# 612_jetracer_esp32s3_030005.net
KiCad netlist of a schematic drawn in EAGLE
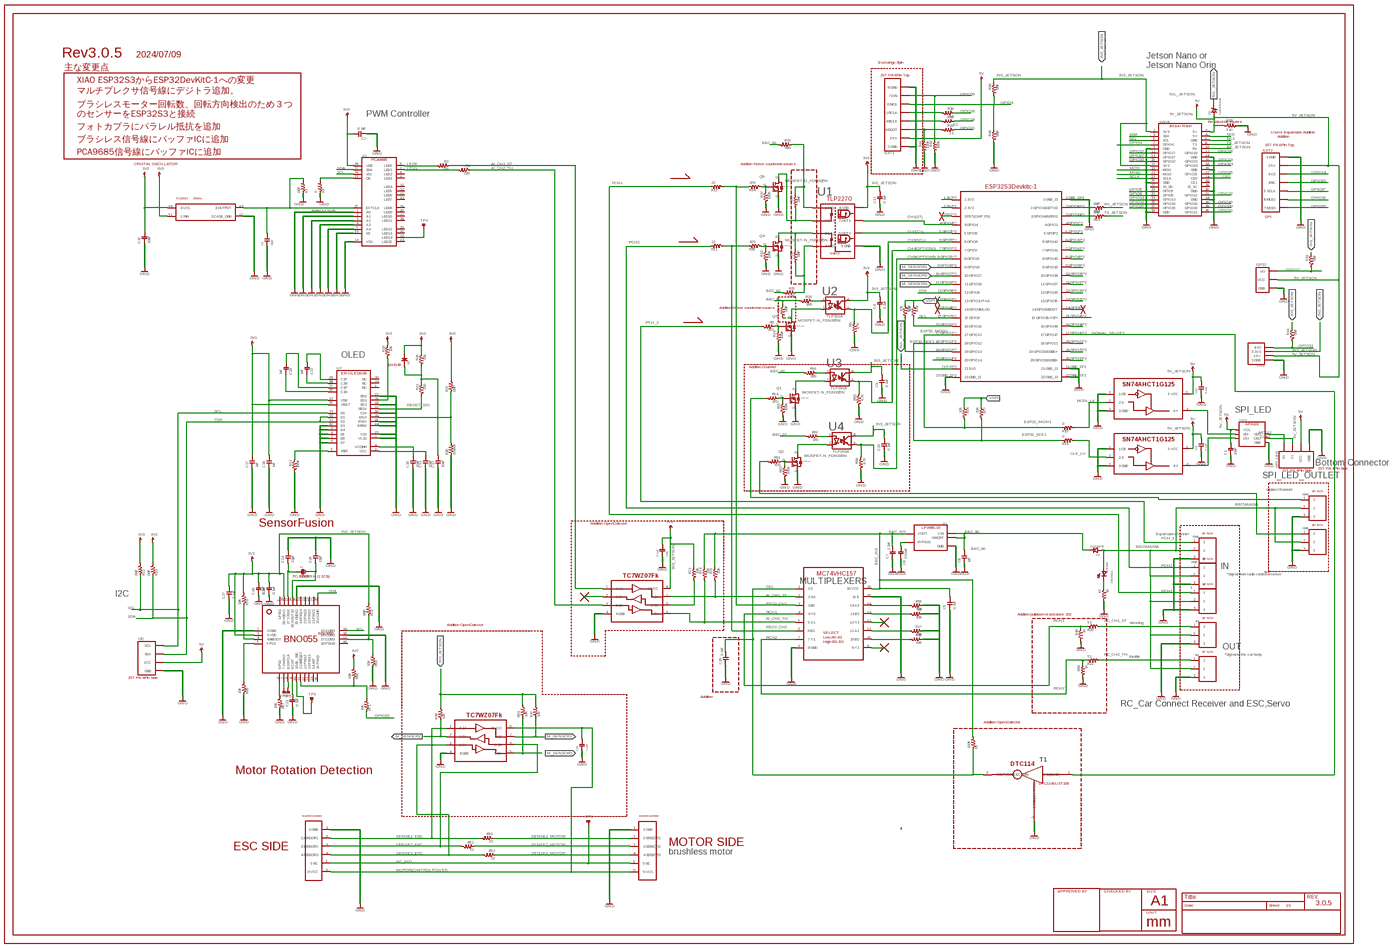
[diagram p0: schematic, sheet 1, overview]
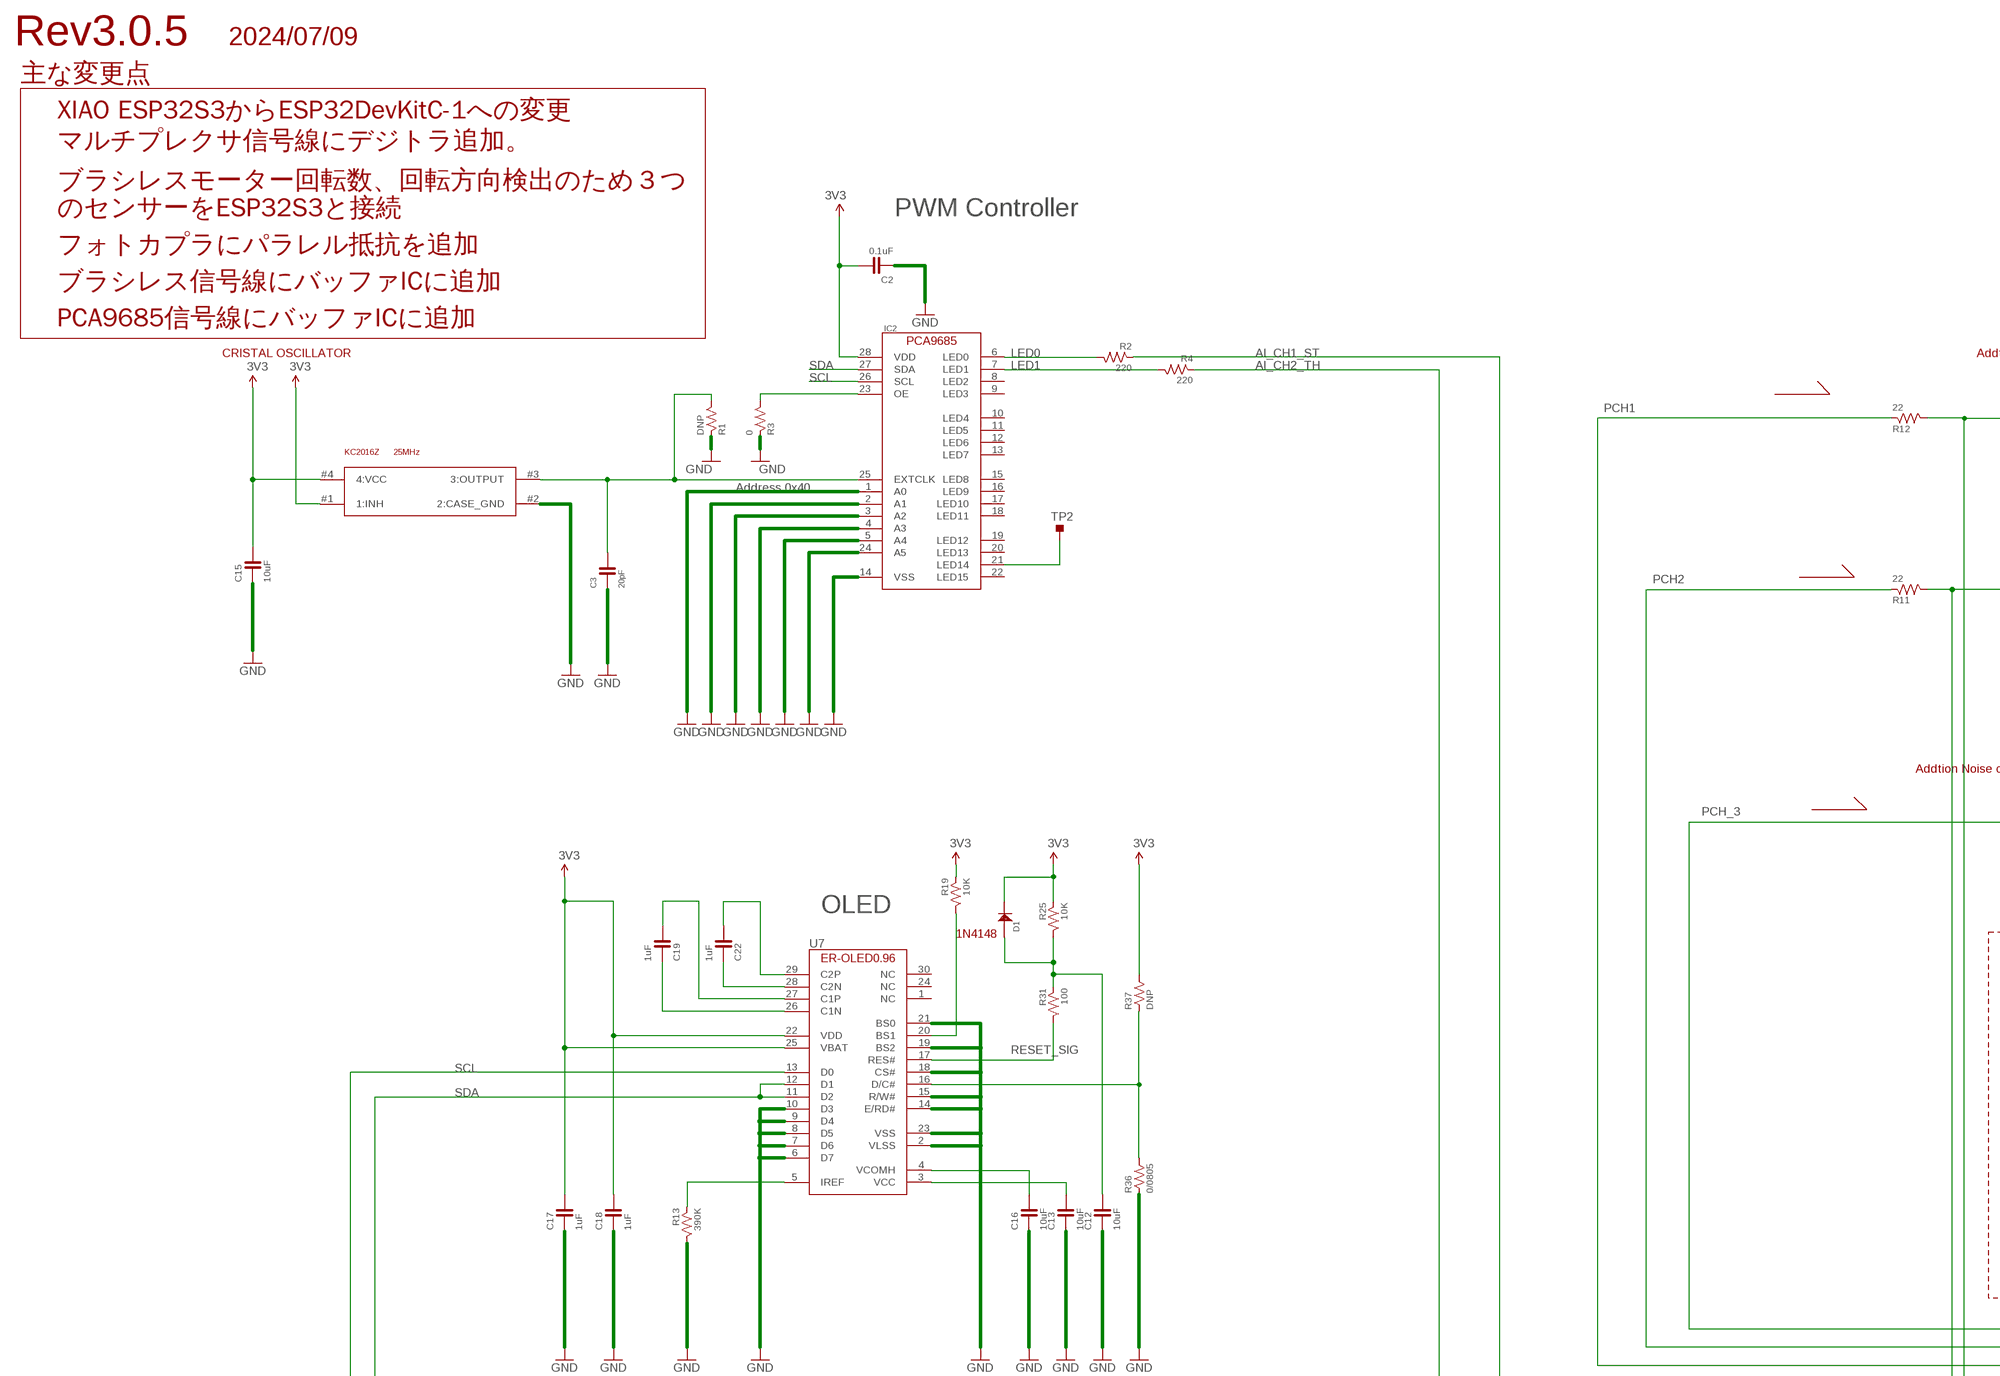
[diagram p1: schematic, sheet 1, part 1 of 4]
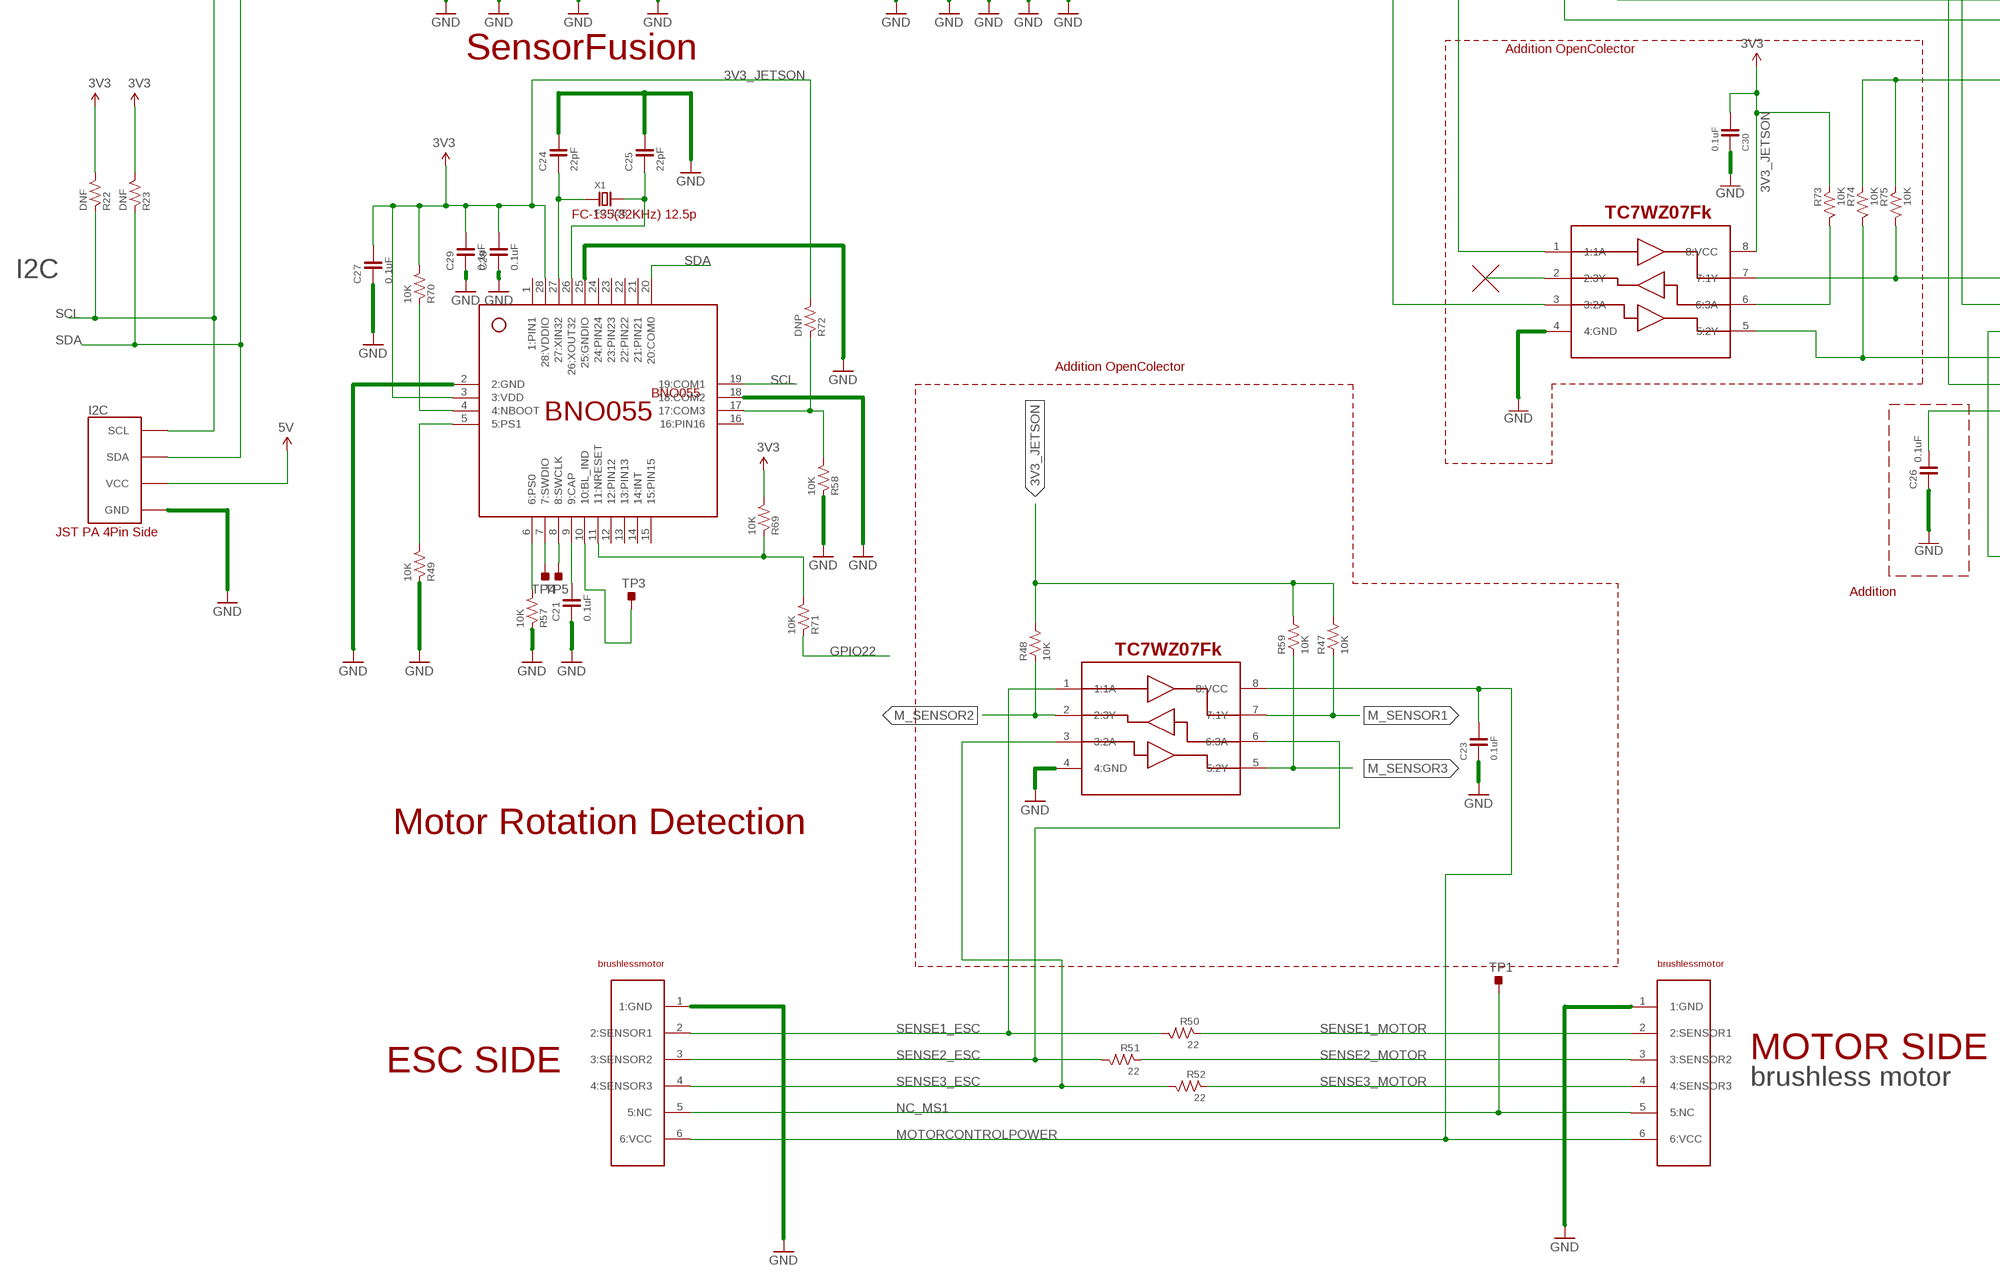
[diagram p2: schematic, sheet 1, part 2 of 4]
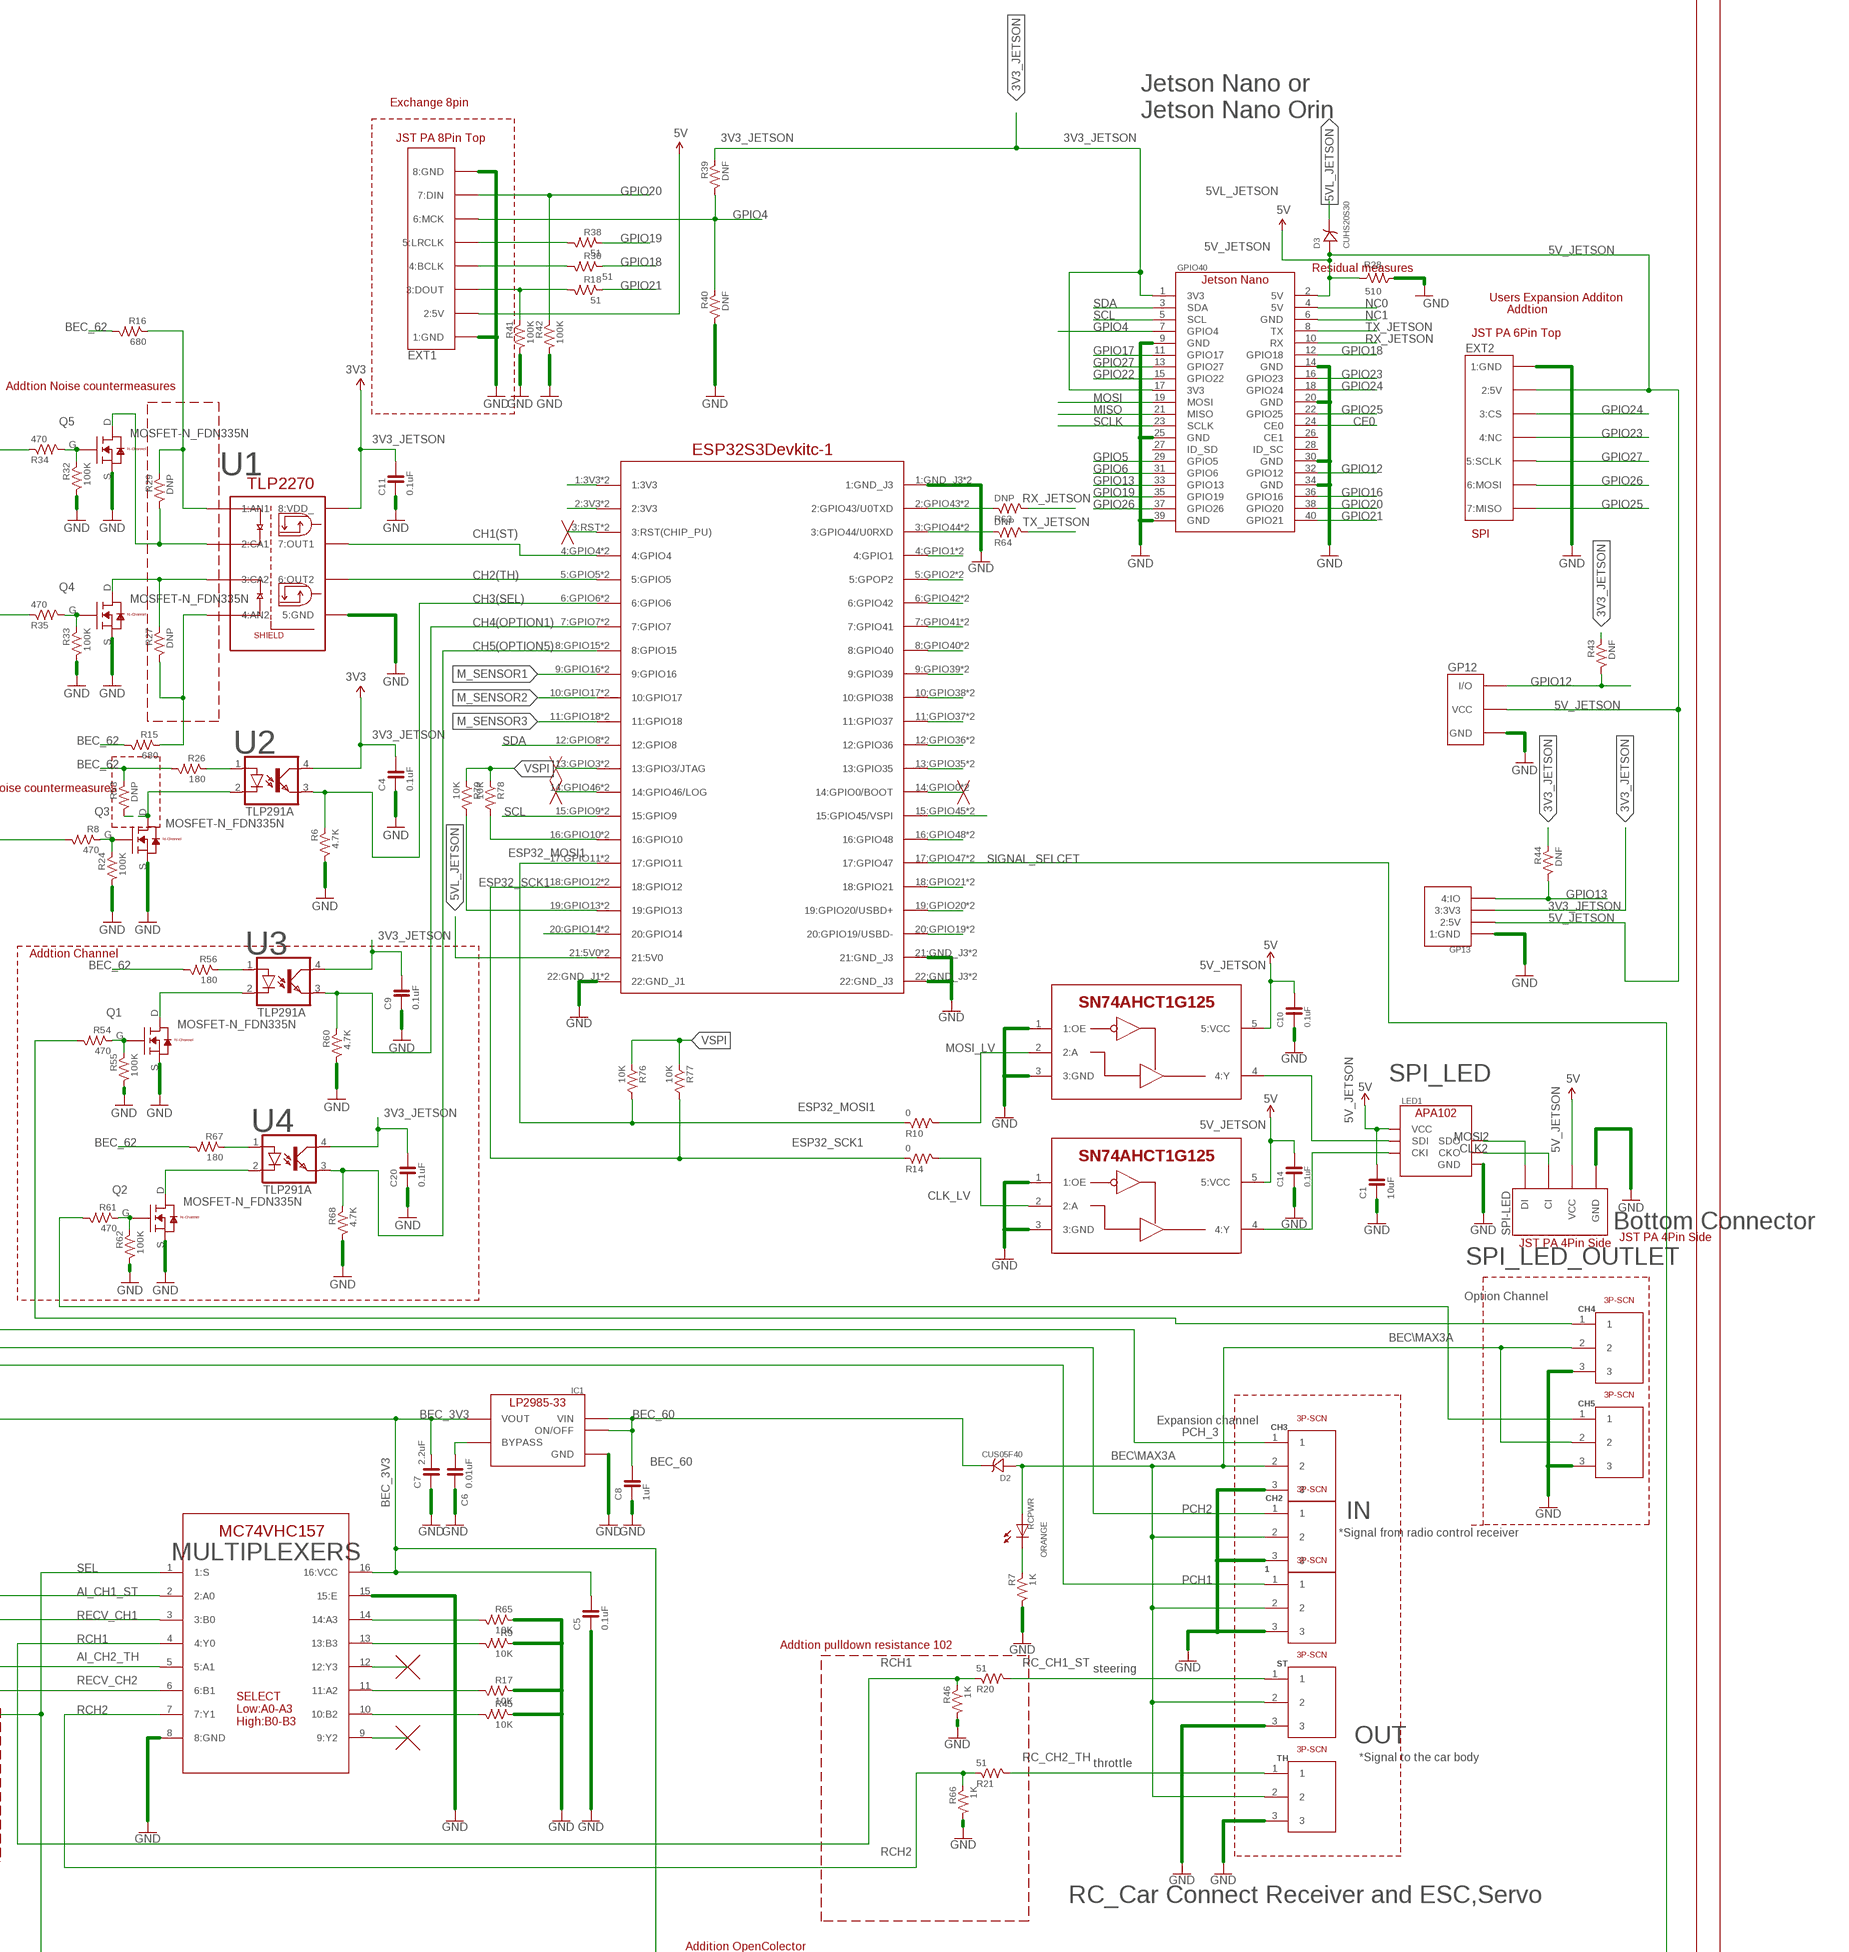
[diagram p3: schematic, sheet 1, part 3 of 4]
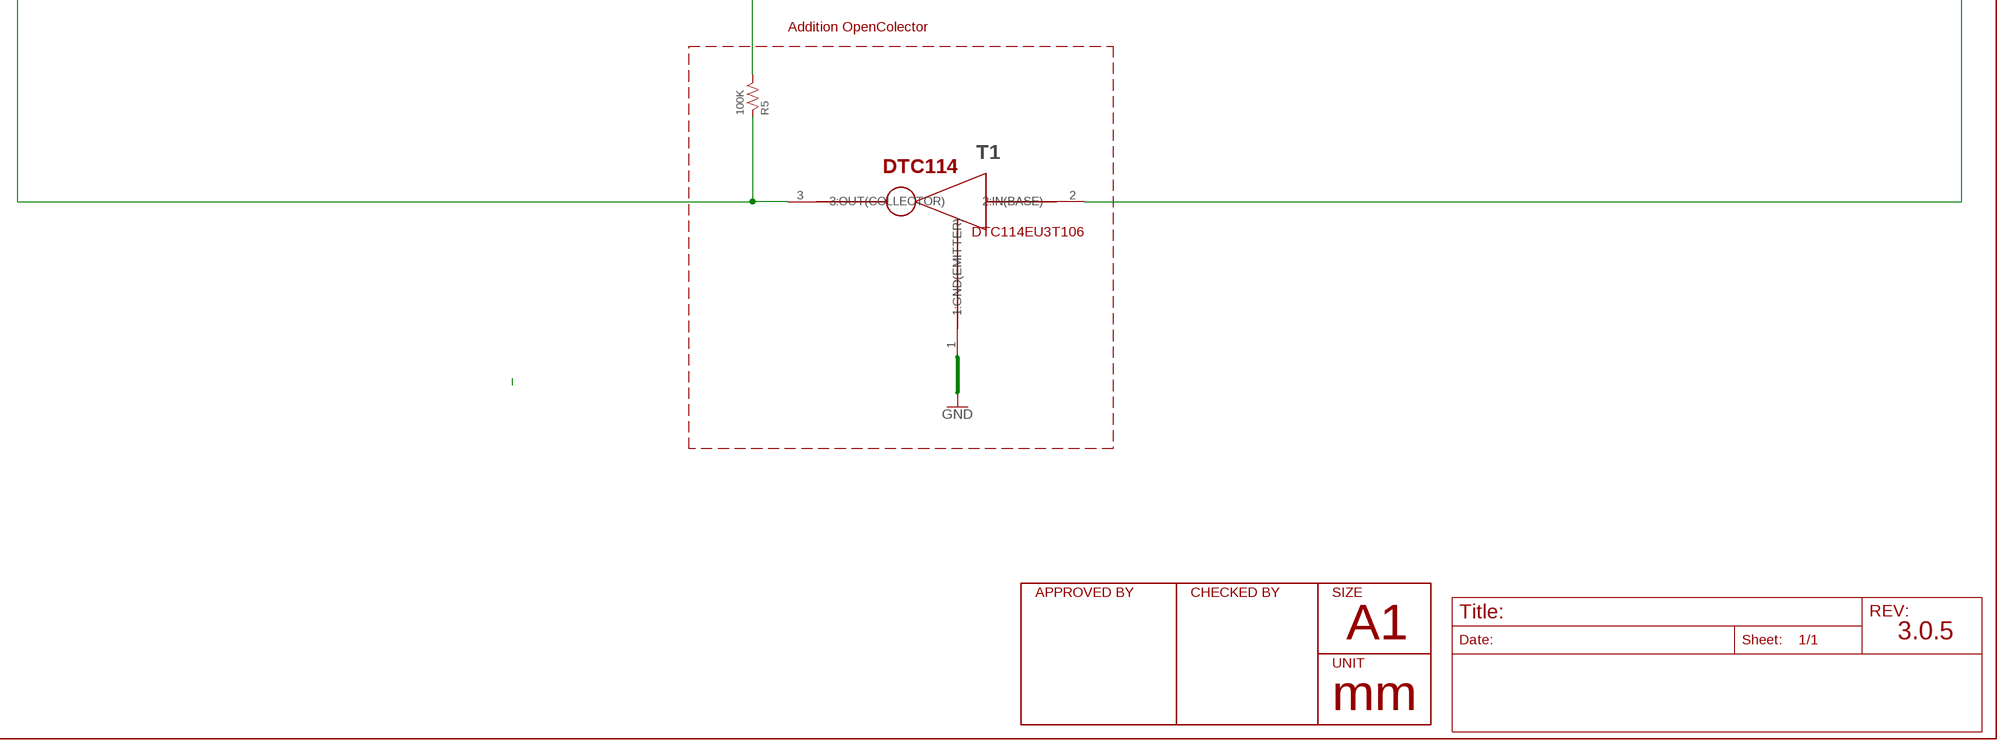
[diagram p4: schematic, sheet 1, part 4 of 4]

(export (version "E")
  (design (tool "Eeschema 10.0.6"))
  (components
    (comp (ref "1")
      (value "3P-SCN")
      (footprint "eagle-import:3P-SCN")
      (libsource (lib "eagle-import") (part "3P-SCN"))
    )
    (comp (ref "C1")
      (value "10uF")
      (footprint "eagle-import:0603")
      (libsource (lib "eagle-import") (part "CAPACITOR-0603"))
    )
    (comp (ref "C2")
      (value "0.1uF")
      (footprint "eagle-import:0603")
      (libsource (lib "eagle-import") (part "CAPACITOR-0603"))
    )
    (comp (ref "C3")
      (value "20pF")
      (footprint "eagle-import:0402")
      (libsource (lib "eagle-import") (part "CAPACITOR-0402"))
    )
    (comp (ref "C4")
      (value "0.1uF")
      (footprint "eagle-import:0603")
      (libsource (lib "eagle-import") (part "CAPACITOR-0603"))
    )
    (comp (ref "C5")
      (value "0.1uF")
      (footprint "eagle-import:0603")
      (fields (field (name "SPICEPREFIX") "C"))
      (libsource (lib "eagle-import") (part "CAPACITOR-0603"))
    )
    (comp (ref "C6")
      (value "0.01uF")
      (footprint "eagle-import:0603")
      (libsource (lib "eagle-import") (part "CAPACITOR-0603"))
    )
    (comp (ref "C7")
      (value "2.2uF")
      (footprint "eagle-import:0603")
      (libsource (lib "eagle-import") (part "CAPACITOR-0603"))
    )
    (comp (ref "C8")
      (value "1uF")
      (footprint "eagle-import:0603")
      (libsource (lib "eagle-import") (part "CAPACITOR-0603"))
    )
    (comp (ref "C9")
      (value "0.1uF")
      (footprint "eagle-import:0603")
      (libsource (lib "eagle-import") (part "CAPACITOR-0603"))
    )
    (comp (ref "C10")
      (value "0.1uF")
      (footprint "eagle-import:0402")
      (libsource (lib "eagle-import") (part "CAPACITOR-0402"))
    )
    (comp (ref "C11")
      (value "0.1uF")
      (footprint "eagle-import:0603")
      (libsource (lib "eagle-import") (part "CAPACITOR-0603"))
    )
    (comp (ref "C12")
      (value "10uF")
      (footprint "eagle-import:0603")
      (libsource (lib "eagle-import") (part "CAPACITOR-0603"))
    )
    (comp (ref "C13")
      (value "10uF")
      (footprint "eagle-import:0603")
      (libsource (lib "eagle-import") (part "CAPACITOR-0603"))
    )
    (comp (ref "C14")
      (value "0.1uF")
      (footprint "eagle-import:0402")
      (libsource (lib "eagle-import") (part "CAPACITOR-0402"))
    )
    (comp (ref "C15")
      (value "10uF")
      (footprint "eagle-import:0603")
      (libsource (lib "eagle-import") (part "CAPACITOR-0603"))
    )
    (comp (ref "C16")
      (value "10uF")
      (footprint "eagle-import:0603")
      (libsource (lib "eagle-import") (part "CAPACITOR-0603"))
    )
    (comp (ref "C17")
      (value "1uF")
      (footprint "eagle-import:0603")
      (libsource (lib "eagle-import") (part "CAPACITOR-0603"))
    )
    (comp (ref "C18")
      (value "1uF")
      (footprint "eagle-import:0603")
      (libsource (lib "eagle-import") (part "CAPACITOR-0603"))
    )
    (comp (ref "C19")
      (value "1uF")
      (footprint "eagle-import:0603")
      (libsource (lib "eagle-import") (part "CAPACITOR-0603"))
    )
    (comp (ref "C20")
      (value "0.1uF")
      (footprint "eagle-import:0603")
      (libsource (lib "eagle-import") (part "CAPACITOR-0603"))
    )
    (comp (ref "C21")
      (value "0.1uF")
      (footprint "eagle-import:0402")
      (libsource (lib "eagle-import") (part "CAPACITOR-0402"))
    )
    (comp (ref "C22")
      (value "1uF")
      (footprint "eagle-import:0603")
      (libsource (lib "eagle-import") (part "CAPACITOR-0603"))
    )
    (comp (ref "C23")
      (value "0.1uF")
      (footprint "eagle-import:0402")
      (libsource (lib "eagle-import") (part "CAPACITOR-0402"))
    )
    (comp (ref "C24")
      (value "22pF")
      (footprint "eagle-import:0402")
      (libsource (lib "eagle-import") (part "CAPACITOR-0402"))
    )
    (comp (ref "C25")
      (value "22pF")
      (footprint "eagle-import:0402")
      (libsource (lib "eagle-import") (part "CAPACITOR-0402"))
    )
    (comp (ref "C26")
      (value "0.1uF")
      (footprint "eagle-import:0603")
      (libsource (lib "eagle-import") (part "CAPACITOR-0603"))
    )
    (comp (ref "C27")
      (value "0.1uF")
      (footprint "eagle-import:0402")
      (libsource (lib "eagle-import") (part "CAPACITOR-0402"))
    )
    (comp (ref "C28")
      (value "0.1uF")
      (footprint "eagle-import:0402")
      (libsource (lib "eagle-import") (part "CAPACITOR-0402"))
    )
    (comp (ref "C29")
      (value "0.1uF")
      (footprint "eagle-import:0402")
      (libsource (lib "eagle-import") (part "CAPACITOR-0402"))
    )
    (comp (ref "C30")
      (value "0.1uF")
      (footprint "eagle-import:0402")
      (libsource (lib "eagle-import") (part "CAPACITOR-0402"))
    )
    (comp (ref "CH2")
      (value "3P-SCN")
      (footprint "eagle-import:3P-SCN")
      (libsource (lib "eagle-import") (part "3P-SCN"))
    )
    (comp (ref "CH3")
      (value "3P-SCN")
      (footprint "eagle-import:3P-SCN")
      (libsource (lib "eagle-import") (part "3P-SCN"))
    )
    (comp (ref "CH4")
      (value "3P-SCN")
      (footprint "eagle-import:3P-SCN")
      (libsource (lib "eagle-import") (part "3P-SCN"))
    )
    (comp (ref "CH5")
      (value "3P-SCN")
      (footprint "eagle-import:3P-SCN")
      (libsource (lib "eagle-import") (part "3P-SCN"))
    )
    (comp (ref "D1")
      (value "1N4148")
      (footprint "eagle-import:1N4148W")
      (libsource (lib "eagle-import") (part "1N4148"))
    )
    (comp (ref "D2")
      (value "CUS05F40")
      (footprint "eagle-import:CUS05F40")
      (libsource (lib "eagle-import") (part "CUS05F40"))
    )
    (comp (ref "D3")
      (value "CUHS20S30")
      (footprint "eagle-import:US2H")
      (libsource (lib "eagle-import") (part "CUHS20S30"))
    )
    (comp (ref "ESC_CON")
      (value "BRUSHLESSMOTOR_CON")
      (footprint "eagle-import:B6B-ZR")
      (libsource (lib "eagle-import") (part "BRUSHLESSMOTOR_CON"))
    )
    (comp (ref "EXT1")
      (value "FABO-I2S-2")
      (footprint "eagle-import:I2S-B08B-PASK-1")
      (libsource (lib "eagle-import") (part "FABO-I2S-2"))
    )
    (comp (ref "EXT2")
      (value "FABO-SPI-7PIN")
      (footprint "eagle-import:SPI-B07B-PASK-1")
      (libsource (lib "eagle-import") (part "FABO-SPI-7PIN"))
    )
    (comp (ref "GP12")
      (value "FABO_BRICK_3PIN-B03B-PASK-1")
      (footprint "eagle-import:FABO_BRICK_3PIN_B03B-PASK-1")
      (libsource (lib "eagle-import") (part "FABO_BRICK_3PIN-B03B-PASK-1"))
    )
    (comp (ref "GP13")
      (value "FABO-GPIO-2G")
      (footprint "eagle-import:GPIO-B04B-PASK-1")
      (libsource (lib "eagle-import") (part "FABO-GPIO-2G"))
    )
    (comp (ref "GPIO40")
      (value "JETSON_NANOJETSON_NANO_OVERALL")
      (footprint "eagle-import:JETSON_NANO_DEMENTION")
      (libsource (lib "eagle-import") (part "JETSON_NANOJETSON_NANO_OVERALL"))
    )
    (comp (ref "I2C")
      (value "FABO-I2C")
      (footprint "eagle-import:I2C-SM04B-PASS-1-FL")
      (libsource (lib "eagle-import") (part "FABO-I2C"))
    )
    (comp (ref "IC1")
      (value "LP2985-33DBVR")
      (footprint "eagle-import:SOT-23-5")
      (libsource (lib "eagle-import") (part "LP2985-33DBVR"))
    )
    (comp (ref "IC2")
      (value "PCA9685PW,BS")
      (footprint "eagle-import:PCA9685")
      (libsource (lib "eagle-import") (part "PCA9685PW,BS"))
    )
    (comp (ref "LED1")
      (value "APA102_IPIXEL")
      (footprint "eagle-import:APA102_2020")
      (libsource (lib "eagle-import") (part "APA102_IPIXEL"))
    )
    (comp (ref "MOTOR")
      (value "BRUSHLESSMOTOR_CON")
      (footprint "eagle-import:B6B-ZR")
      (libsource (lib "eagle-import") (part "BRUSHLESSMOTOR_CON"))
    )
    (comp (ref "Q1")
      (value "MOSFET-N_FDN335N")
      (footprint "eagle-import:SUPERSOT-3")
      (libsource (lib "eagle-import") (part "MOSFET-N_FDN335N"))
    )
    (comp (ref "Q2")
      (value "MOSFET-N_FDN335N")
      (footprint "eagle-import:SUPERSOT-3")
      (libsource (lib "eagle-import") (part "MOSFET-N_FDN335N"))
    )
    (comp (ref "Q3")
      (value "MOSFET-N_FDN335N")
      (footprint "eagle-import:SUPERSOT-3")
      (libsource (lib "eagle-import") (part "MOSFET-N_FDN335N"))
    )
    (comp (ref "Q4")
      (value "MOSFET-N_FDN335N")
      (footprint "eagle-import:SUPERSOT-3")
      (libsource (lib "eagle-import") (part "MOSFET-N_FDN335N"))
    )
    (comp (ref "Q5")
      (value "MOSFET-N_FDN335N")
      (footprint "eagle-import:SUPERSOT-3")
      (libsource (lib "eagle-import") (part "MOSFET-N_FDN335N"))
    )
    (comp (ref "R1")
      (value "DNP")
      (footprint "eagle-import:0603")
      (libsource (lib "eagle-import") (part "RESISTOR-0603"))
    )
    (comp (ref "R2")
      (value "220")
      (footprint "eagle-import:0402")
      (fields (field (name "SPICEPREFIX") "R"))
      (libsource (lib "eagle-import") (part "RESISTOR-0402"))
    )
    (comp (ref "R3")
      (value "0")
      (footprint "eagle-import:0603")
      (libsource (lib "eagle-import") (part "RESISTOR-0603"))
    )
    (comp (ref "R4")
      (value "220")
      (footprint "eagle-import:0402")
      (fields (field (name "SPICEPREFIX") "R"))
      (libsource (lib "eagle-import") (part "RESISTOR-0402"))
    )
    (comp (ref "R5")
      (value "100K")
      (footprint "eagle-import:0603")
      (libsource (lib "eagle-import") (part "RESISTOR-0603"))
    )
    (comp (ref "R6")
      (value "4.7K")
      (footprint "eagle-import:0603")
      (libsource (lib "eagle-import") (part "RESISTOR-0603"))
    )
    (comp (ref "R7")
      (value "1K")
      (footprint "eagle-import:0402")
      (fields (field (name "SPICEPREFIX") "R"))
      (libsource (lib "eagle-import") (part "RESISTOR-0402"))
    )
    (comp (ref "R8")
      (value "470")
      (footprint "eagle-import:0603")
      (libsource (lib "eagle-import") (part "RESISTOR-0603"))
    )
    (comp (ref "R9")
      (value "10K")
      (footprint "eagle-import:0402")
      (fields (field (name "SPICEPREFIX") "R"))
      (libsource (lib "eagle-import") (part "RESISTOR-0402"))
    )
    (comp (ref "R10")
      (value "0")
      (footprint "eagle-import:0603")
      (libsource (lib "eagle-import") (part "RESISTOR-0603"))
    )
    (comp (ref "R11")
      (value "22")
      (footprint "eagle-import:0603")
      (libsource (lib "eagle-import") (part "RESISTOR-0603"))
    )
    (comp (ref "R12")
      (value "22")
      (footprint "eagle-import:0603")
      (libsource (lib "eagle-import") (part "RESISTOR-0603"))
    )
    (comp (ref "R13")
      (value "390K")
      (footprint "eagle-import:0603")
      (libsource (lib "eagle-import") (part "RESISTOR-0603"))
    )
    (comp (ref "R14")
      (value "0")
      (footprint "eagle-import:0603")
      (libsource (lib "eagle-import") (part "RESISTOR-0603"))
    )
    (comp (ref "R15")
      (value "680")
      (footprint "eagle-import:0603")
      (libsource (lib "eagle-import") (part "RESISTOR-0603"))
    )
    (comp (ref "R16")
      (value "680")
      (footprint "eagle-import:0603")
      (libsource (lib "eagle-import") (part "RESISTOR-0603"))
    )
    (comp (ref "R17")
      (value "10K")
      (footprint "eagle-import:0402")
      (fields (field (name "SPICEPREFIX") "R"))
      (libsource (lib "eagle-import") (part "RESISTOR-0402"))
    )
    (comp (ref "R18")
      (value "51")
      (footprint "eagle-import:0603")
      (libsource (lib "eagle-import") (part "RESISTOR-0603"))
    )
    (comp (ref "R19")
      (value "10K")
      (footprint "eagle-import:0603")
      (libsource (lib "eagle-import") (part "RESISTOR-0603"))
    )
    (comp (ref "R20")
      (value "51")
      (footprint "eagle-import:0603")
      (libsource (lib "eagle-import") (part "RESISTOR-0603"))
    )
    (comp (ref "R21")
      (value "51")
      (footprint "eagle-import:0603")
      (libsource (lib "eagle-import") (part "RESISTOR-0603"))
    )
    (comp (ref "R22")
      (value "DNF")
      (footprint "eagle-import:0603")
      (libsource (lib "eagle-import") (part "RESISTOR-0603"))
    )
    (comp (ref "R23")
      (value "DNF")
      (footprint "eagle-import:0603")
      (libsource (lib "eagle-import") (part "RESISTOR-0603"))
    )
    (comp (ref "R24")
      (value "100K")
      (footprint "eagle-import:0603")
      (libsource (lib "eagle-import") (part "RESISTOR-0603"))
    )
    (comp (ref "R25")
      (value "10K")
      (footprint "eagle-import:0603")
      (libsource (lib "eagle-import") (part "RESISTOR-0603"))
    )
    (comp (ref "R26")
      (value "180")
      (footprint "eagle-import:0603")
      (libsource (lib "eagle-import") (part "RESISTOR-0603"))
    )
    (comp (ref "R27")
      (value "DNP")
      (footprint "eagle-import:0603")
      (libsource (lib "eagle-import") (part "RESISTOR-0603"))
    )
    (comp (ref "R28")
      (value "510")
      (footprint "eagle-import:0805")
      (libsource (lib "eagle-import") (part "RESISTOR-0805"))
    )
    (comp (ref "R29")
      (value "DNP")
      (footprint "eagle-import:0603")
      (libsource (lib "eagle-import") (part "RESISTOR-0603"))
    )
    (comp (ref "R30")
      (value "51")
      (footprint "eagle-import:0603")
      (libsource (lib "eagle-import") (part "RESISTOR-0603"))
    )
    (comp (ref "R31")
      (value "100")
      (footprint "eagle-import:0603")
      (libsource (lib "eagle-import") (part "RESISTOR-0603"))
    )
    (comp (ref "R32")
      (value "100K")
      (footprint "eagle-import:0603")
      (libsource (lib "eagle-import") (part "RESISTOR-0603"))
    )
    (comp (ref "R33")
      (value "100K")
      (footprint "eagle-import:0603")
      (libsource (lib "eagle-import") (part "RESISTOR-0603"))
    )
    (comp (ref "R34")
      (value "470")
      (footprint "eagle-import:0603")
      (libsource (lib "eagle-import") (part "RESISTOR-0603"))
    )
    (comp (ref "R35")
      (value "470")
      (footprint "eagle-import:0603")
      (libsource (lib "eagle-import") (part "RESISTOR-0603"))
    )
    (comp (ref "R36")
      (value "0/0805")
      (footprint "eagle-import:0805")
      (libsource (lib "eagle-import") (part "RESISTOR-0805"))
    )
    (comp (ref "R37")
      (value "DNP")
      (footprint "eagle-import:0805")
      (fields (field (name "SPICEPREFIX") "R"))
      (libsource (lib "eagle-import") (part "RESISTOR-0805"))
    )
    (comp (ref "R38")
      (value "51")
      (footprint "eagle-import:0603")
      (libsource (lib "eagle-import") (part "RESISTOR-0603"))
    )
    (comp (ref "R39")
      (value "DNF")
      (footprint "eagle-import:0603")
      (libsource (lib "eagle-import") (part "RESISTOR-0603"))
    )
    (comp (ref "R40")
      (value "DNF")
      (footprint "eagle-import:0603")
      (libsource (lib "eagle-import") (part "RESISTOR-0603"))
    )
    (comp (ref "R41")
      (value "100K")
      (footprint "eagle-import:0603")
      (libsource (lib "eagle-import") (part "RESISTOR-0603"))
    )
    (comp (ref "R42")
      (value "100K")
      (footprint "eagle-import:0603")
      (libsource (lib "eagle-import") (part "RESISTOR-0603"))
    )
    (comp (ref "R43")
      (value "DNF")
      (footprint "eagle-import:0603")
      (libsource (lib "eagle-import") (part "RESISTOR-0603"))
    )
    (comp (ref "R44")
      (value "DNF")
      (footprint "eagle-import:0603")
      (libsource (lib "eagle-import") (part "RESISTOR-0603"))
    )
    (comp (ref "R45")
      (value "10K")
      (footprint "eagle-import:0402")
      (fields (field (name "SPICEPREFIX") "R"))
      (libsource (lib "eagle-import") (part "RESISTOR-0402"))
    )
    (comp (ref "R46")
      (value "1K")
      (footprint "eagle-import:0402")
      (fields (field (name "SPICEPREFIX") "R"))
      (libsource (lib "eagle-import") (part "RESISTOR-0402"))
    )
    (comp (ref "R47")
      (value "10K")
      (footprint "eagle-import:0402")
      (libsource (lib "eagle-import") (part "RESISTOR-0402"))
    )
    (comp (ref "R48")
      (value "10K")
      (footprint "eagle-import:0402")
      (libsource (lib "eagle-import") (part "RESISTOR-0402"))
    )
    (comp (ref "R49")
      (value "10K")
      (footprint "eagle-import:0402")
      (libsource (lib "eagle-import") (part "RESISTOR-0402"))
    )
    (comp (ref "R50")
      (value "22")
      (footprint "eagle-import:0603")
      (libsource (lib "eagle-import") (part "RESISTOR-0603"))
    )
    (comp (ref "R51")
      (value "22")
      (footprint "eagle-import:0603")
      (libsource (lib "eagle-import") (part "RESISTOR-0603"))
    )
    (comp (ref "R52")
      (value "22")
      (footprint "eagle-import:0603")
      (libsource (lib "eagle-import") (part "RESISTOR-0603"))
    )
    (comp (ref "R53")
      (value "DNP")
      (footprint "eagle-import:0603")
      (libsource (lib "eagle-import") (part "RESISTOR-0603"))
    )
    (comp (ref "R54")
      (value "470")
      (footprint "eagle-import:0603")
      (libsource (lib "eagle-import") (part "RESISTOR-0603"))
    )
    (comp (ref "R55")
      (value "100K")
      (footprint "eagle-import:0603")
      (libsource (lib "eagle-import") (part "RESISTOR-0603"))
    )
    (comp (ref "R56")
      (value "180")
      (footprint "eagle-import:0603")
      (libsource (lib "eagle-import") (part "RESISTOR-0603"))
    )
    (comp (ref "R57")
      (value "10K")
      (footprint "eagle-import:0402")
      (libsource (lib "eagle-import") (part "RESISTOR-0402"))
    )
    (comp (ref "R58")
      (value "10K")
      (footprint "eagle-import:0402")
      (libsource (lib "eagle-import") (part "RESISTOR-0402"))
    )
    (comp (ref "R59")
      (value "10K")
      (footprint "eagle-import:0402")
      (libsource (lib "eagle-import") (part "RESISTOR-0402"))
    )
    (comp (ref "R60")
      (value "4.7K")
      (footprint "eagle-import:0603")
      (libsource (lib "eagle-import") (part "RESISTOR-0603"))
    )
    (comp (ref "R61")
      (value "470")
      (footprint "eagle-import:0603")
      (libsource (lib "eagle-import") (part "RESISTOR-0603"))
    )
    (comp (ref "R62")
      (value "100K")
      (footprint "eagle-import:0603")
      (libsource (lib "eagle-import") (part "RESISTOR-0603"))
    )
    (comp (ref "R63")
      (value "DNP")
      (footprint "eagle-import:0603")
      (libsource (lib "eagle-import") (part "RESISTOR-0603"))
    )
    (comp (ref "R64")
      (value "DNP")
      (footprint "eagle-import:0603")
      (libsource (lib "eagle-import") (part "RESISTOR-0603"))
    )
    (comp (ref "R65")
      (value "10K")
      (footprint "eagle-import:0402")
      (fields (field (name "SPICEPREFIX") "R"))
      (libsource (lib "eagle-import") (part "RESISTOR-0402"))
    )
    (comp (ref "R66")
      (value "1K")
      (footprint "eagle-import:0402")
      (fields (field (name "SPICEPREFIX") "R"))
      (libsource (lib "eagle-import") (part "RESISTOR-0402"))
    )
    (comp (ref "R67")
      (value "180")
      (footprint "eagle-import:0603")
      (libsource (lib "eagle-import") (part "RESISTOR-0603"))
    )
    (comp (ref "R68")
      (value "4.7K")
      (footprint "eagle-import:0603")
      (libsource (lib "eagle-import") (part "RESISTOR-0603"))
    )
    (comp (ref "R69")
      (value "10K")
      (footprint "eagle-import:0402")
      (libsource (lib "eagle-import") (part "RESISTOR-0402"))
    )
    (comp (ref "R70")
      (value "10K")
      (footprint "eagle-import:0402")
      (libsource (lib "eagle-import") (part "RESISTOR-0402"))
    )
    (comp (ref "R71")
      (value "10K")
      (footprint "eagle-import:0402")
      (libsource (lib "eagle-import") (part "RESISTOR-0402"))
    )
    (comp (ref "R72")
      (value "DNP")
      (footprint "eagle-import:0402")
      (fields (field (name "SPICEPREFIX") "R"))
      (libsource (lib "eagle-import") (part "RESISTOR-0402"))
    )
    (comp (ref "R73")
      (value "10K")
      (footprint "eagle-import:0402")
      (fields (field (name "SPICEPREFIX") "R"))
      (libsource (lib "eagle-import") (part "RESISTOR-0402"))
    )
    (comp (ref "R74")
      (value "10K")
      (footprint "eagle-import:0402")
      (fields (field (name "SPICEPREFIX") "R"))
      (libsource (lib "eagle-import") (part "RESISTOR-0402"))
    )
    (comp (ref "R75")
      (value "10K")
      (footprint "eagle-import:0402")
      (fields (field (name "SPICEPREFIX") "R"))
      (libsource (lib "eagle-import") (part "RESISTOR-0402"))
    )
    (comp (ref "R76")
      (value "10K")
      (footprint "eagle-import:0402")
      (fields (field (name "SPICEPREFIX") "R"))
      (libsource (lib "eagle-import") (part "RESISTOR-0402"))
    )
    (comp (ref "R77")
      (value "10K")
      (footprint "eagle-import:0402")
      (fields (field (name "SPICEPREFIX") "R"))
      (libsource (lib "eagle-import") (part "RESISTOR-0402"))
    )
    (comp (ref "R78")
      (value "10K")
      (footprint "eagle-import:0402")
      (fields (field (name "SPICEPREFIX") "R"))
      (libsource (lib "eagle-import") (part "RESISTOR-0402"))
    )
    (comp (ref "R79")
      (value "10K")
      (footprint "eagle-import:0402")
      (fields (field (name "SPICEPREFIX") "R"))
      (libsource (lib "eagle-import") (part "RESISTOR-0402"))
    )
    (comp (ref "RCPWR")
      (value "ORANGE")
      (footprint "eagle-import:0603")
      (libsource (lib "eagle-import") (part "LED-0603"))
    )
    (comp (ref "SPI-LED")
      (value "FABO-SPI-LED")
      (footprint "eagle-import:SPI-SM04B-PASS-1-FL")
      (libsource (lib "eagle-import") (part "FABO-SPI-LED"))
    )
    (comp (ref "ST")
      (value "3P-SCN")
      (footprint "eagle-import:3P-SCN")
      (libsource (lib "eagle-import") (part "3P-SCN"))
    )
    (comp (ref "T1")
      (value "DTC114EU3")
      (footprint "eagle-import:SOT-323FL_SC-85(UMT3F)")
      (libsource (lib "eagle-import") (part "DTC114EU3"))
    )
    (comp (ref "TH")
      (value "3P-SCN")
      (footprint "eagle-import:3P-SCN")
      (libsource (lib "eagle-import") (part "3P-SCN"))
    )
    (comp (ref "TP1")
      (value "TESTPOINT_TPS-SMD-10SN")
      (footprint "eagle-import:TESTPOINT_SMD-10SN")
      (libsource (lib "eagle-import") (part "TESTPOINT_TPS-SMD-10SN"))
    )
    (comp (ref "TP2")
      (value "TESTPOINT_TPS-SMD-10SN")
      (footprint "eagle-import:TESTPOINT_SMD-10SN")
      (libsource (lib "eagle-import") (part "TESTPOINT_TPS-SMD-10SN"))
    )
    (comp (ref "TP3")
      (value "TESTPOINT_TPS-SMD-10SN")
      (footprint "eagle-import:TESTPOINT_SMD-10SN")
      (libsource (lib "eagle-import") (part "TESTPOINT_TPS-SMD-10SN"))
    )
    (comp (ref "TP4")
      (value "TESTPOINT_TPS-SMD-10SN")
      (footprint "eagle-import:TESTPOINT_SMD-10SN")
      (libsource (lib "eagle-import") (part "TESTPOINT_TPS-SMD-10SN"))
    )
    (comp (ref "TP5")
      (value "TESTPOINT_TPS-SMD-10SN")
      (footprint "eagle-import:TESTPOINT_SMD-10SN")
      (libsource (lib "eagle-import") (part "TESTPOINT_TPS-SMD-10SN"))
    )
    (comp (ref "U$1")
      (value "MC74VHC157")
      (footprint "eagle-import:MC74VHC157_TSSOP-16")
      (libsource (lib "eagle-import") (part "MC74VHC157"))
    )
    (comp (ref "U$3")
      (value "TC7WZ07FK")
      (footprint "eagle-import:SOT-765")
      (libsource (lib "eagle-import") (part "TC7WZ07FK"))
    )
    (comp (ref "U$5")
      (value "TC7WZ07FK")
      (footprint "eagle-import:SOT-765")
      (libsource (lib "eagle-import") (part "TC7WZ07FK"))
    )
    (comp (ref "U$9")
      (value "SN74AHCT1G125")
      (footprint "eagle-import:SOT-1DOT1")
      (libsource (lib "eagle-import") (part "SN74AHCT1G125"))
    )
    (comp (ref "U$10")
      (value "SN74AHCT1G125")
      (footprint "eagle-import:SOT-1DOT1")
      (libsource (lib "eagle-import") (part "SN74AHCT1G125"))
    )
    (comp (ref "U$11")
      (value "KC2016Z")
      (footprint "eagle-import:KC2016Z")
      (libsource (lib "eagle-import") (part "KC2016Z"))
    )
    (comp (ref "U$13")
      (value "BNO055")
      (footprint "eagle-import:LGA")
      (libsource (lib "eagle-import") (part "BNO055"))
    )
    (comp (ref "U$14")
      (value "ESP32S3DEVKITC-1-DUAL")
      (footprint "eagle-import:ESP32S3DEVKITC-1-DUAL")
      (libsource (lib "eagle-import") (part "ESP32S3DEVKITC-1-DUAL"))
    )
    (comp (ref "U1")
      (value "TLP2270")
      (footprint "eagle-import:TLP2270")
      (libsource (lib "eagle-import") (part "TLP2270"))
    )
    (comp (ref "U2")
      (value "TLP291A")
      (footprint "eagle-import:11-3C1")
      (libsource (lib "eagle-import") (part "TLP291A"))
    )
    (comp (ref "U3")
      (value "TLP291A")
      (footprint "eagle-import:11-3C1")
      (libsource (lib "eagle-import") (part "TLP291A"))
    )
    (comp (ref "U4")
      (value "TLP291A")
      (footprint "eagle-import:11-3C1")
      (libsource (lib "eagle-import") (part "TLP291A"))
    )
    (comp (ref "U7")
      (value "ER-OLED0.96-1ER-CON30HT-1")
      (footprint "eagle-import:ER-CON30HT-1")
      (libsource (lib "eagle-import") (part "ER-OLED0.96-1ER-CON30HT-1"))
    )
    (comp (ref "X1")
      (value "FC-135")
      (footprint "eagle-import:FC-135")
      (libsource (lib "eagle-import") (part "FC-135"))
    )
  )
  (nets
    (net (code "1") (name "/AI_CH1_ST") (class "Default")
      (node (ref "R2") (pin "1") (pinfunction "1_1") (pintype "bidirectional"))
      (node (ref "U$5") (pin "1") (pinfunction "1:1A_1") (pintype "input"))
    )
    (net (code "2") (name "/AI_CH2_TH") (class "Default")
      (node (ref "R4") (pin "1") (pinfunction "1_1") (pintype "bidirectional"))
      (node (ref "U$5") (pin "3") (pinfunction "3:2A_3") (pintype "input"))
    )
    (net (code "3") (name "/BEC\\MAX3A") (class "Default")
      (node (ref "1") (pin "2") (pinfunction "2_2") (pintype "power_in"))
      (node (ref "CH2") (pin "2") (pinfunction "2_2") (pintype "power_in"))
      (node (ref "CH3") (pin "2") (pinfunction "2_2") (pintype "power_in"))
      (node (ref "CH4") (pin "2") (pinfunction "2_2") (pintype "power_in"))
      (node (ref "CH5") (pin "2") (pinfunction "2_2") (pintype "power_in"))
      (node (ref "D2") (pin "A") (pinfunction "ANODE_A") (pintype "bidirectional"))
      (node (ref "RCPWR") (pin "ANODE") (pinfunction "ANODE_ANODE") (pintype "passive"))
      (node (ref "ST") (pin "2") (pinfunction "2_2") (pintype "power_in"))
      (node (ref "TH") (pin "2") (pinfunction "2_2") (pintype "power_in"))
    )
    (net (code "4") (name "/BEC_3V3") (class "Default")
      (node (ref "C5") (pin "2") (pinfunction "2_2") (pintype "passive"))
      (node (ref "C7") (pin "2") (pinfunction "2_2") (pintype "passive"))
      (node (ref "IC1") (pin "5") (pinfunction "VOUT_5") (pintype "output"))
      (node (ref "R5") (pin "2") (pinfunction "2_2") (pintype "bidirectional"))
      (node (ref "R74") (pin "1") (pinfunction "1_1") (pintype "bidirectional"))
      (node (ref "R75") (pin "1") (pinfunction "1_1") (pintype "bidirectional"))
      (node (ref "U$1") (pin "16") (pinfunction "16:VCC_16") (pintype "bidirectional"))
    )
    (net (code "5") (name "/BEC_60") (class "Default")
      (node (ref "C8") (pin "2") (pinfunction "2_2") (pintype "passive"))
      (node (ref "D2") (pin "C") (pinfunction "CATHODE_C") (pintype "bidirectional"))
      (node (ref "IC1") (pin "1") (pinfunction "VIN_1") (pintype "input"))
      (node (ref "IC1") (pin "3") (pinfunction "ON/OFF_3") (pintype "input"))
    )
    (net (code "6") (name "/BEC_62") (class "Default")
      (node (ref "R15") (pin "2") (pinfunction "2_2") (pintype "bidirectional"))
      (node (ref "R16") (pin "2") (pinfunction "2_2") (pintype "bidirectional"))
      (node (ref "R26") (pin "2") (pinfunction "2_2") (pintype "bidirectional"))
      (node (ref "R53") (pin "1") (pinfunction "1_1") (pintype "bidirectional"))
      (node (ref "R56") (pin "2") (pinfunction "2_2") (pintype "bidirectional"))
      (node (ref "R67") (pin "2") (pinfunction "2_2") (pintype "bidirectional"))
    )
    (net (code "7") (name "/CE0") (class "Default")
      (node (ref "GPIO40") (pin "24") (pinfunction "CE0_24") (pintype "bidirectional"))
    )
    (net (code "8") (name "/CH1(ST)") (class "Default")
      (node (ref "U$14") (pin "4:GPIO4") (pinfunction "4:GPIO4_4:GPIO4") (pintype "bidirectional"))
      (node (ref "U$14") (pin "4:GPIO4_L") (pinfunction "4:GPIO4_4:GPIO4_L") (pintype "bidirectional"))
      (node (ref "U1") (pin "7") (pinfunction "7:OUT1_7") (pintype "bidirectional"))
    )
    (net (code "9") (name "/CH2(TH)") (class "Default")
      (node (ref "U$14") (pin "5:GPIO5") (pinfunction "5:GPIO5_5:GPIO5") (pintype "bidirectional"))
      (node (ref "U$14") (pin "5:GPIO5_L") (pinfunction "5:GPIO5_5:GPIO5_L") (pintype "bidirectional"))
      (node (ref "U1") (pin "6") (pinfunction "6:OUT2_6") (pintype "bidirectional"))
    )
    (net (code "10") (name "/CH3(SEL)") (class "Default")
      (node (ref "R6") (pin "1") (pinfunction "1_1") (pintype "bidirectional"))
      (node (ref "U$14") (pin "6:GPIO6") (pinfunction "6:GPIO6_6:GPIO6") (pintype "bidirectional"))
      (node (ref "U$14") (pin "6:GPIO6_L") (pinfunction "6:GPIO6_6:GPIO6_L") (pintype "bidirectional"))
      (node (ref "U2") (pin "3") (pinfunction "EMI_3") (pintype "passive"))
    )
    (net (code "11") (name "/CH4(OPTION1)") (class "Default")
      (node (ref "R60") (pin "1") (pinfunction "1_1") (pintype "bidirectional"))
      (node (ref "U$14") (pin "7:GPIO7") (pinfunction "7:GPIO7_7:GPIO7") (pintype "bidirectional"))
      (node (ref "U$14") (pin "7:GPIO7_L") (pinfunction "7:GPIO7_7:GPIO7_L") (pintype "bidirectional"))
      (node (ref "U3") (pin "3") (pinfunction "EMI_3") (pintype "passive"))
    )
    (net (code "12") (name "/CH5(OPTION5)") (class "Default")
      (node (ref "R68") (pin "1") (pinfunction "1_1") (pintype "bidirectional"))
      (node (ref "U$14") (pin "8:GPIO15") (pinfunction "8:GPIO15_8:GPIO15") (pintype "bidirectional"))
      (node (ref "U$14") (pin "8:GPIO15_L") (pinfunction "8:GPIO15_8:GPIO15_L") (pintype "bidirectional"))
      (node (ref "U4") (pin "3") (pinfunction "EMI_3") (pintype "passive"))
    )
    (net (code "13") (name "/CLK2") (class "Default")
      (node (ref "LED1") (pin "CKO") (pinfunction "CKO_CKO") (pintype "bidirectional"))
      (node (ref "SPI-LED") (pin "CI") (pinfunction "CI_CI") (pintype "bidirectional"))
    )
    (net (code "14") (name "/CLK_LV") (class "Default")
      (node (ref "R14") (pin "2") (pinfunction "2_2") (pintype "bidirectional"))
      (node (ref "U$10") (pin "2") (pinfunction "2:A_2") (pintype "input"))
    )
    (net (code "15") (name "/ESP32_MOSI1") (class "Default")
      (node (ref "R10") (pin "1") (pinfunction "1_1") (pintype "bidirectional"))
      (node (ref "R76") (pin "2") (pinfunction "2_2") (pintype "bidirectional"))
      (node (ref "U$14") (pin "17:GPIO11") (pinfunction "17:GPIO11_17:GPIO11") (pintype "bidirectional"))
      (node (ref "U$14") (pin "17:GPIO11_L") (pinfunction "17:GPIO11_17:GPIO11_L") (pintype "bidirectional"))
    )
    (net (code "16") (name "/ESP32_SCK1") (class "Default")
      (node (ref "R14") (pin "1") (pinfunction "1_1") (pintype "bidirectional"))
      (node (ref "R77") (pin "2") (pinfunction "2_2") (pintype "bidirectional"))
      (node (ref "U$14") (pin "18:GPIO12") (pinfunction "18:GPIO12_18:GPIO12") (pintype "bidirectional"))
      (node (ref "U$14") (pin "18:GPIO12_L") (pinfunction "18:GPIO12_18:GPIO12_L") (pintype "bidirectional"))
    )
    (net (code "17") (name "/GPIO4") (class "Default")
      (node (ref "EXT1") (pin "6:MCK") (pinfunction "6:MCK_6:MCK") (pintype "output"))
      (node (ref "GPIO40") (pin "7") (pinfunction "GPIO4_7") (pintype "bidirectional"))
      (node (ref "R39") (pin "2") (pinfunction "2_2") (pintype "bidirectional"))
      (node (ref "R40") (pin "1") (pinfunction "1_1") (pintype "bidirectional"))
    )
    (net (code "18") (name "/GPIO5") (class "Default")
      (node (ref "GPIO40") (pin "29") (pinfunction "GPIO5_29") (pintype "bidirectional"))
    )
    (net (code "19") (name "/GPIO6") (class "Default")
      (node (ref "GPIO40") (pin "31") (pinfunction "GPIO6_31") (pintype "bidirectional"))
    )
    (net (code "20") (name "/GPIO12") (class "Default")
      (node (ref "GP12") (pin "I/O") (pinfunction "I/O_I/O") (pintype "bidirectional"))
      (node (ref "GPIO40") (pin "32") (pinfunction "GPIO12_32") (pintype "bidirectional"))
      (node (ref "R43") (pin "2") (pinfunction "2_2") (pintype "bidirectional"))
    )
    (net (code "21") (name "/GPIO13") (class "Default")
      (node (ref "GP13") (pin "IO") (pinfunction "4:IO_IO") (pintype "bidirectional"))
      (node (ref "GPIO40") (pin "33") (pinfunction "GPIO13_33") (pintype "bidirectional"))
      (node (ref "R44") (pin "2") (pinfunction "2_2") (pintype "bidirectional"))
    )
    (net (code "22") (name "/GPIO16") (class "Default")
      (node (ref "GPIO40") (pin "36") (pinfunction "GPIO16_36") (pintype "bidirectional"))
    )
    (net (code "23") (name "/GPIO17") (class "Default")
      (node (ref "GPIO40") (pin "11") (pinfunction "GPIO17_11") (pintype "bidirectional"))
    )
    (net (code "24") (name "/GPIO18") (class "Default")
      (node (ref "GPIO40") (pin "12") (pinfunction "GPIO18_12") (pintype "bidirectional"))
      (node (ref "R30") (pin "1") (pinfunction "1_1") (pintype "bidirectional"))
    )
    (net (code "25") (name "/GPIO19") (class "Default")
      (node (ref "GPIO40") (pin "35") (pinfunction "GPIO19_35") (pintype "bidirectional"))
      (node (ref "R38") (pin "1") (pinfunction "1_1") (pintype "bidirectional"))
    )
    (net (code "26") (name "/GPIO20") (class "Default")
      (node (ref "EXT1") (pin "7:DIN") (pinfunction "7:DIN_7:DIN") (pintype "output"))
      (node (ref "GPIO40") (pin "38") (pinfunction "GPIO20_38") (pintype "bidirectional"))
      (node (ref "R42") (pin "1") (pinfunction "1_1") (pintype "bidirectional"))
    )
    (net (code "27") (name "/GPIO21") (class "Default")
      (node (ref "GPIO40") (pin "40") (pinfunction "GPIO21_40") (pintype "bidirectional"))
      (node (ref "R18") (pin "1") (pinfunction "1_1") (pintype "bidirectional"))
    )
    (net (code "28") (name "/GPIO22") (class "Default")
      (node (ref "GPIO40") (pin "15") (pinfunction "GPIO22_15") (pintype "bidirectional"))
      (node (ref "R71") (pin "1") (pinfunction "1_1") (pintype "bidirectional"))
    )
    (net (code "29") (name "/GPIO23") (class "Default")
      (node (ref "EXT2") (pin "4") (pinfunction "4:NC_4") (pintype "bidirectional"))
      (node (ref "GPIO40") (pin "16") (pinfunction "GPIO23_16") (pintype "bidirectional"))
    )
    (net (code "30") (name "/GPIO24") (class "Default")
      (node (ref "EXT2") (pin "3") (pinfunction "3:CS_3") (pintype "bidirectional"))
      (node (ref "GPIO40") (pin "18") (pinfunction "GPIO24_18") (pintype "bidirectional"))
    )
    (net (code "31") (name "/GPIO25") (class "Default")
      (node (ref "EXT2") (pin "7") (pinfunction "7:MISO_7") (pintype "bidirectional"))
      (node (ref "GPIO40") (pin "22") (pinfunction "GPIO25_22") (pintype "bidirectional"))
    )
    (net (code "32") (name "/GPIO26") (class "Default")
      (node (ref "EXT2") (pin "6") (pinfunction "6:MOSI_6") (pintype "bidirectional"))
      (node (ref "GPIO40") (pin "37") (pinfunction "GPIO26_37") (pintype "bidirectional"))
    )
    (net (code "33") (name "/GPIO27") (class "Default")
      (node (ref "EXT2") (pin "5") (pinfunction "5:SCLK_5") (pintype "bidirectional"))
      (node (ref "GPIO40") (pin "13") (pinfunction "GPIO27_13") (pintype "bidirectional"))
    )
    (net (code "34") (name "/LED0") (class "Default")
      (node (ref "IC2") (pin "6") (pinfunction "LED0_6") (pintype "bidirectional"))
      (node (ref "R2") (pin "2") (pinfunction "2_2") (pintype "bidirectional"))
    )
    (net (code "35") (name "/LED1") (class "Default")
      (node (ref "IC2") (pin "7") (pinfunction "LED1_7") (pintype "bidirectional"))
      (node (ref "R4") (pin "2") (pinfunction "2_2") (pintype "bidirectional"))
    )
    (net (code "36") (name "/MISO") (class "Default")
      (node (ref "GPIO40") (pin "21") (pinfunction "MISO_21") (pintype "bidirectional"))
    )
    (net (code "37") (name "/MOSI") (class "Default")
      (node (ref "GPIO40") (pin "19") (pinfunction "MOSI_19") (pintype "bidirectional"))
    )
    (net (code "38") (name "/MOSI2") (class "Default")
      (node (ref "LED1") (pin "SDO") (pinfunction "SDO_SDO") (pintype "bidirectional"))
      (node (ref "SPI-LED") (pin "DI") (pinfunction "DI_DI") (pintype "bidirectional"))
    )
    (net (code "39") (name "/MOSI_LV") (class "Default")
      (node (ref "R10") (pin "2") (pinfunction "2_2") (pintype "bidirectional"))
      (node (ref "U$9") (pin "2") (pinfunction "2:A_2") (pintype "input"))
    )
    (net (code "40") (name "/MOTORCONTROLPOWER") (class "Default")
      (node (ref "C23") (pin "2") (pinfunction "2_2") (pintype "passive"))
      (node (ref "ESC_CON") (pin "6") (pinfunction "6:VCC_6") (pintype "bidirectional"))
      (node (ref "MOTOR") (pin "6") (pinfunction "6:VCC_6") (pintype "bidirectional"))
      (node (ref "U$3") (pin "8") (pinfunction "8:VCC_8") (pintype "power_in"))
    )
    (net (code "41") (name "/NC0") (class "Default")
      (node (ref "GPIO40") (pin "4") (pinfunction "5V_4") (pintype "bidirectional"))
    )
    (net (code "42") (name "/NC1") (class "Default")
      (node (ref "GPIO40") (pin "6") (pinfunction "GND_6") (pintype "bidirectional"))
    )
    (net (code "43") (name "/NC_MS1") (class "Default")
      (node (ref "ESC_CON") (pin "5") (pinfunction "5:NC_5") (pintype "bidirectional"))
      (node (ref "MOTOR") (pin "5") (pinfunction "5:NC_5") (pintype "bidirectional"))
      (node (ref "TP1") (pin "TP") (pinfunction "TP_TP") (pintype "passive"))
    )
    (net (code "44") (name "/PCH1") (class "Default")
      (node (ref "1") (pin "1") (pinfunction "1_1") (pintype "bidirectional"))
      (node (ref "R12") (pin "1") (pinfunction "1_1") (pintype "bidirectional"))
    )
    (net (code "45") (name "/PCH2") (class "Default")
      (node (ref "CH2") (pin "1") (pinfunction "1_1") (pintype "bidirectional"))
      (node (ref "R11") (pin "1") (pinfunction "1_1") (pintype "bidirectional"))
    )
    (net (code "46") (name "/PCH_3") (class "Default")
      (node (ref "CH3") (pin "1") (pinfunction "1_1") (pintype "bidirectional"))
      (node (ref "R8") (pin "2") (pinfunction "2_2") (pintype "bidirectional"))
    )
    (net (code "47") (name "/RCH1") (class "Default")
      (node (ref "R20") (pin "1") (pinfunction "1_1") (pintype "bidirectional"))
      (node (ref "R46") (pin "1") (pinfunction "1_1") (pintype "bidirectional"))
      (node (ref "U$1") (pin "4") (pinfunction "4:Y0_4") (pintype "bidirectional"))
    )
    (net (code "48") (name "/RCH2") (class "Default")
      (node (ref "R21") (pin "1") (pinfunction "1_1") (pintype "bidirectional"))
      (node (ref "R66") (pin "1") (pinfunction "1_1") (pintype "bidirectional"))
      (node (ref "U$1") (pin "7") (pinfunction "7:Y1_7") (pintype "bidirectional"))
    )
    (net (code "49") (name "/RC_CH1_ST") (class "Default")
      (node (ref "R20") (pin "2") (pinfunction "2_2") (pintype "bidirectional"))
      (node (ref "ST") (pin "1") (pinfunction "1_1") (pintype "bidirectional"))
    )
    (net (code "50") (name "/RC_CH2_TH") (class "Default")
      (node (ref "R21") (pin "2") (pinfunction "2_2") (pintype "bidirectional"))
      (node (ref "TH") (pin "1") (pinfunction "1_1") (pintype "bidirectional"))
    )
    (net (code "51") (name "/RECV_CH1") (class "Default")
      (node (ref "R12") (pin "2") (pinfunction "2_2") (pintype "bidirectional"))
      (node (ref "R34") (pin "1") (pinfunction "1_1") (pintype "bidirectional"))
      (node (ref "U$1") (pin "3") (pinfunction "3:B0_3") (pintype "bidirectional"))
    )
    (net (code "52") (name "/RECV_CH2") (class "Default")
      (node (ref "R11") (pin "2") (pinfunction "2_2") (pintype "bidirectional"))
      (node (ref "R35") (pin "1") (pinfunction "1_1") (pintype "bidirectional"))
      (node (ref "U$1") (pin "6") (pinfunction "6:B1_6") (pintype "bidirectional"))
    )
    (net (code "53") (name "/RESET_SIG") (class "Default")
      (node (ref "R31") (pin "2") (pinfunction "2_2") (pintype "bidirectional"))
      (node (ref "U7") (pin "17") (pinfunction "RES#_17") (pintype "bidirectional"))
    )
    (net (code "54") (name "/RX_JETSON") (class "Default")
      (node (ref "GPIO40") (pin "10") (pinfunction "RX_10") (pintype "bidirectional"))
      (node (ref "R63") (pin "2") (pinfunction "2_2") (pintype "bidirectional"))
    )
    (net (code "55") (name "/SCL") (class "Default")
      (node (ref "GPIO40") (pin "5") (pinfunction "SCL_5") (pintype "bidirectional"))
      (node (ref "I2C") (pin "SCL") (pinfunction "SCL_SCL") (pintype "bidirectional"))
      (node (ref "IC2") (pin "26") (pinfunction "SCL_26") (pintype "bidirectional"))
      (node (ref "R22") (pin "1") (pinfunction "1_1") (pintype "bidirectional"))
      (node (ref "U$13") (pin "19") (pinfunction "19:COM1_19") (pintype "bidirectional"))
      (node (ref "U$14") (pin "15:GPIO9") (pinfunction "15:GPIO9_15:GPIO9") (pintype "bidirectional"))
      (node (ref "U$14") (pin "15:GPIO9_L") (pinfunction "15:GPIO9_15:GPIO9_L") (pintype "bidirectional"))
      (node (ref "U7") (pin "13") (pinfunction "D0_13") (pintype "bidirectional"))
    )
    (net (code "56") (name "/SCLK") (class "Default")
      (node (ref "GPIO40") (pin "23") (pinfunction "SCLK_23") (pintype "bidirectional"))
    )
    (net (code "57") (name "/SDA") (class "Default")
      (node (ref "GPIO40") (pin "3") (pinfunction "SDA_3") (pintype "bidirectional"))
      (node (ref "I2C") (pin "SDA") (pinfunction "SDA_SDA") (pintype "bidirectional"))
      (node (ref "IC2") (pin "27") (pinfunction "SDA_27") (pintype "bidirectional"))
      (node (ref "R23") (pin "1") (pinfunction "1_1") (pintype "bidirectional"))
      (node (ref "U$13") (pin "20") (pinfunction "20:COM0_20") (pintype "bidirectional"))
      (node (ref "U$14") (pin "12:GPIO8") (pinfunction "12:GPIO8_12:GPIO8") (pintype "bidirectional"))
      (node (ref "U$14") (pin "12:GPIO8_L") (pinfunction "12:GPIO8_12:GPIO8_L") (pintype "bidirectional"))
      (node (ref "U7") (pin "11") (pinfunction "D2_11") (pintype "bidirectional"))
      (node (ref "U7") (pin "12") (pinfunction "D1_12") (pintype "bidirectional"))
    )
    (net (code "58") (name "/SEL") (class "Default")
      (node (ref "C26") (pin "2") (pinfunction "2_2") (pintype "passive"))
      (node (ref "R5") (pin "1") (pinfunction "1_1") (pintype "bidirectional"))
      (node (ref "T1") (pin "3") (pinfunction "3:OUT(COLLECTOR)_3") (pintype "output"))
      (node (ref "U$1") (pin "1") (pinfunction "1:S_1") (pintype "bidirectional"))
    )
    (net (code "59") (name "/SENSE1_ESC") (class "Default")
      (node (ref "ESC_CON") (pin "2") (pinfunction "2:SENSOR1_2") (pintype "bidirectional"))
      (node (ref "R50") (pin "2") (pinfunction "2_2") (pintype "bidirectional"))
      (node (ref "U$3") (pin "1") (pinfunction "1:1A_1") (pintype "input"))
    )
    (net (code "60") (name "/SENSE1_MOTOR") (class "Default")
      (node (ref "MOTOR") (pin "2") (pinfunction "2:SENSOR1_2") (pintype "bidirectional"))
      (node (ref "R50") (pin "1") (pinfunction "1_1") (pintype "bidirectional"))
    )
    (net (code "61") (name "/SENSE2_ESC") (class "Default")
      (node (ref "ESC_CON") (pin "3") (pinfunction "3:SENSOR2_3") (pintype "bidirectional"))
      (node (ref "R51") (pin "2") (pinfunction "2_2") (pintype "bidirectional"))
      (node (ref "U$3") (pin "6") (pinfunction "6:3A_6") (pintype "input"))
    )
    (net (code "62") (name "/SENSE2_MOTOR") (class "Default")
      (node (ref "MOTOR") (pin "3") (pinfunction "3:SENSOR2_3") (pintype "bidirectional"))
      (node (ref "R51") (pin "1") (pinfunction "1_1") (pintype "bidirectional"))
    )
    (net (code "63") (name "/SENSE3_ESC") (class "Default")
      (node (ref "ESC_CON") (pin "4") (pinfunction "4:SENSOR3_4") (pintype "bidirectional"))
      (node (ref "R52") (pin "2") (pinfunction "2_2") (pintype "bidirectional"))
      (node (ref "U$3") (pin "3") (pinfunction "3:2A_3") (pintype "input"))
    )
    (net (code "64") (name "/SENSE3_MOTOR") (class "Default")
      (node (ref "MOTOR") (pin "4") (pinfunction "4:SENSOR3_4") (pintype "bidirectional"))
      (node (ref "R52") (pin "1") (pinfunction "1_1") (pintype "bidirectional"))
    )
    (net (code "65") (name "/SIGNAL_SELCET") (class "Default")
      (node (ref "T1") (pin "2") (pinfunction "2:IN(BASE)_2") (pintype "input"))
      (node (ref "U$14") (pin "17:GPIO47") (pinfunction "17:GPIO47_17:GPIO47") (pintype "bidirectional"))
      (node (ref "U$14") (pin "17:GPIO47_R") (pinfunction "17:GPIO47_17:GPIO47_R") (pintype "bidirectional"))
    )
    (net (code "66") (name "/TX_JETSON") (class "Default")
      (node (ref "GPIO40") (pin "8") (pinfunction "TX_8") (pintype "bidirectional"))
      (node (ref "R64") (pin "2") (pinfunction "2_2") (pintype "bidirectional"))
    )
    (net (code "67") (name "3V3_JETSON") (class "Default")
      (node (ref "C11") (pin "2") (pinfunction "2_2") (pintype "passive"))
      (node (ref "C15") (pin "2") (pinfunction "2_2") (pintype "passive"))
      (node (ref "C17") (pin "2") (pinfunction "2_2") (pintype "passive"))
      (node (ref "C18") (pin "2") (pinfunction "2_2") (pintype "passive"))
      (node (ref "C2") (pin "2") (pinfunction "2_2") (pintype "passive"))
      (node (ref "C20") (pin "2") (pinfunction "2_2") (pintype "passive"))
      (node (ref "C27") (pin "2") (pinfunction "2_2") (pintype "passive"))
      (node (ref "C28") (pin "2") (pinfunction "2_2") (pintype "passive"))
      (node (ref "C29") (pin "2") (pinfunction "2_2") (pintype "passive"))
      (node (ref "C30") (pin "2") (pinfunction "2_2") (pintype "passive"))
      (node (ref "C4") (pin "2") (pinfunction "2_2") (pintype "passive"))
      (node (ref "C9") (pin "2") (pinfunction "2_2") (pintype "passive"))
      (node (ref "D1") (pin "CATHODE") (pinfunction "CATHODE_CATHODE") (pintype "bidirectional"))
      (node (ref "GP13") (pin "3V3") (pinfunction "3:3V3_3V3") (pintype "bidirectional"))
      (node (ref "GPIO40") (pin "1") (pinfunction "3V3_1") (pintype "bidirectional"))
      (node (ref "GPIO40") (pin "17") (pinfunction "3V3_17") (pintype "bidirectional"))
      (node (ref "IC2") (pin "28") (pinfunction "VDD_28") (pintype "bidirectional"))
      (node (ref "R19") (pin "1") (pinfunction "1_1") (pintype "bidirectional"))
      (node (ref "R22") (pin "2") (pinfunction "2_2") (pintype "bidirectional"))
      (node (ref "R23") (pin "2") (pinfunction "2_2") (pintype "bidirectional"))
      (node (ref "R25") (pin "1") (pinfunction "1_1") (pintype "bidirectional"))
      (node (ref "R37") (pin "2") (pinfunction "2_2") (pintype "bidirectional"))
      (node (ref "R39") (pin "1") (pinfunction "1_1") (pintype "bidirectional"))
      (node (ref "R43") (pin "1") (pinfunction "1_1") (pintype "bidirectional"))
      (node (ref "R44") (pin "1") (pinfunction "1_1") (pintype "bidirectional"))
      (node (ref "R47") (pin "2") (pinfunction "2_2") (pintype "bidirectional"))
      (node (ref "R48") (pin "2") (pinfunction "2_2") (pintype "bidirectional"))
      (node (ref "R59") (pin "2") (pinfunction "2_2") (pintype "bidirectional"))
      (node (ref "R69") (pin "2") (pinfunction "2_2") (pintype "bidirectional"))
      (node (ref "R70") (pin "2") (pinfunction "2_2") (pintype "bidirectional"))
      (node (ref "R72") (pin "2") (pinfunction "2_2") (pintype "bidirectional"))
      (node (ref "R73") (pin "1") (pinfunction "1_1") (pintype "bidirectional"))
      (node (ref "U$11") (pin "#1") (pinfunction "1:INH_#1") (pintype "bidirectional"))
      (node (ref "U$11") (pin "#4") (pinfunction "4:VCC_#4") (pintype "bidirectional"))
      (node (ref "U$13") (pin "28") (pinfunction "28:VDDIO_28") (pintype "power_in"))
      (node (ref "U$13") (pin "3") (pinfunction "3:VDD_3") (pintype "power_in"))
      (node (ref "U$5") (pin "8") (pinfunction "8:VCC_8") (pintype "power_in"))
      (node (ref "U1") (pin "8") (pinfunction "8:VDD__8") (pintype "bidirectional"))
      (node (ref "U2") (pin "4") (pinfunction "COL_4") (pintype "passive"))
      (node (ref "U3") (pin "4") (pinfunction "COL_4") (pintype "passive"))
      (node (ref "U4") (pin "4") (pinfunction "COL_4") (pintype "passive"))
      (node (ref "U7") (pin "22") (pinfunction "VDD_22") (pintype "bidirectional"))
      (node (ref "U7") (pin "25") (pinfunction "VBAT_25") (pintype "bidirectional"))
    )
    (net (code "68") (name "5V") (class "Default")
      (node (ref "C1") (pin "2") (pinfunction "2_2") (pintype "passive"))
      (node (ref "C10") (pin "2") (pinfunction "2_2") (pintype "passive"))
      (node (ref "C14") (pin "2") (pinfunction "2_2") (pintype "passive"))
      (node (ref "D3") (pin "A") (pinfunction "ANODE_A") (pintype "passive"))
      (node (ref "EXT1") (pin "2:5V") (pinfunction "2:5V_2:5V") (pintype "power_in"))
      (node (ref "EXT2") (pin "2") (pinfunction "2:5V_2") (pintype "bidirectional"))
      (node (ref "GP12") (pin "VCC") (pinfunction "VCC_VCC") (pintype "bidirectional"))
      (node (ref "GP13") (pin "5V") (pinfunction "2:5V_5V") (pintype "bidirectional"))
      (node (ref "GPIO40") (pin "2") (pinfunction "5V_2") (pintype "bidirectional"))
      (node (ref "I2C") (pin "5V") (pinfunction "VCC_5V") (pintype "bidirectional"))
      (node (ref "LED1") (pin "VCC") (pinfunction "VCC_VCC") (pintype "bidirectional"))
      (node (ref "R28") (pin "2") (pinfunction "2_2") (pintype "bidirectional"))
      (node (ref "SPI-LED") (pin "5V") (pinfunction "VCC_5V") (pintype "bidirectional"))
      (node (ref "U$10") (pin "5") (pinfunction "5:VCC_5") (pintype "power_in"))
      (node (ref "U$9") (pin "5") (pinfunction "5:VCC_5") (pintype "power_in"))
    )
    (net (code "69") (name "5VL_JETSON") (class "Default")
      (node (ref "D3") (pin "K") (pinfunction "CATHODE_K") (pintype "passive"))
      (node (ref "U$14") (pin "21:5V0") (pinfunction "21:5V0_21:5V0") (pintype "power_in"))
      (node (ref "U$14") (pin "21:5V0_L") (pinfunction "21:5V0_21:5V0_L") (pintype "power_in"))
    )
    (net (code "70") (name "GND") (class "Default")
      (node (ref "1") (pin "3") (pinfunction "3_3") (pintype "power_in"))
      (node (ref "C1") (pin "1") (pinfunction "1_1") (pintype "passive"))
      (node (ref "C10") (pin "1") (pinfunction "1_1") (pintype "passive"))
      (node (ref "C11") (pin "1") (pinfunction "1_1") (pintype "passive"))
      (node (ref "C12") (pin "1") (pinfunction "1_1") (pintype "passive"))
      (node (ref "C13") (pin "1") (pinfunction "1_1") (pintype "passive"))
      (node (ref "C14") (pin "1") (pinfunction "1_1") (pintype "passive"))
      (node (ref "C15") (pin "1") (pinfunction "1_1") (pintype "passive"))
      (node (ref "C16") (pin "1") (pinfunction "1_1") (pintype "passive"))
      (node (ref "C17") (pin "1") (pinfunction "1_1") (pintype "passive"))
      (node (ref "C18") (pin "1") (pinfunction "1_1") (pintype "passive"))
      (node (ref "C2") (pin "1") (pinfunction "1_1") (pintype "passive"))
      (node (ref "C20") (pin "1") (pinfunction "1_1") (pintype "passive"))
      (node (ref "C21") (pin "1") (pinfunction "1_1") (pintype "passive"))
      (node (ref "C23") (pin "1") (pinfunction "1_1") (pintype "passive"))
      (node (ref "C24") (pin "2") (pinfunction "2_2") (pintype "passive"))
      (node (ref "C25") (pin "2") (pinfunction "2_2") (pintype "passive"))
      (node (ref "C26") (pin "1") (pinfunction "1_1") (pintype "passive"))
      (node (ref "C27") (pin "1") (pinfunction "1_1") (pintype "passive"))
      (node (ref "C28") (pin "1") (pinfunction "1_1") (pintype "passive"))
      (node (ref "C29") (pin "1") (pinfunction "1_1") (pintype "passive"))
      (node (ref "C3") (pin "1") (pinfunction "1_1") (pintype "passive"))
      (node (ref "C30") (pin "1") (pinfunction "1_1") (pintype "passive"))
      (node (ref "C4") (pin "1") (pinfunction "1_1") (pintype "passive"))
      (node (ref "C5") (pin "1") (pinfunction "1_1") (pintype "passive"))
      (node (ref "C6") (pin "1") (pinfunction "1_1") (pintype "passive"))
      (node (ref "C7") (pin "1") (pinfunction "1_1") (pintype "passive"))
      (node (ref "C8") (pin "1") (pinfunction "1_1") (pintype "passive"))
      (node (ref "C9") (pin "1") (pinfunction "1_1") (pintype "passive"))
      (node (ref "CH2") (pin "3") (pinfunction "3_3") (pintype "power_in"))
      (node (ref "CH3") (pin "3") (pinfunction "3_3") (pintype "power_in"))
      (node (ref "CH4") (pin "3") (pinfunction "3_3") (pintype "power_in"))
      (node (ref "CH5") (pin "3") (pinfunction "3_3") (pintype "power_in"))
      (node (ref "ESC_CON") (pin "1") (pinfunction "1:GND_1") (pintype "bidirectional"))
      (node (ref "EXT1") (pin "1:GND") (pinfunction "1:GND_1:GND") (pintype "power_in"))
      (node (ref "EXT1") (pin "8:GND") (pinfunction "8:GND_8:GND") (pintype "power_in"))
      (node (ref "EXT2") (pin "1") (pinfunction "1:GND_1") (pintype "bidirectional"))
      (node (ref "GP12") (pin "GND") (pinfunction "GND_GND") (pintype "bidirectional"))
      (node (ref "GP13") (pin "GND") (pinfunction "1:GND_GND") (pintype "bidirectional"))
      (node (ref "GPIO40") (pin "14") (pinfunction "GND_14") (pintype "bidirectional"))
      (node (ref "GPIO40") (pin "20") (pinfunction "GND_20") (pintype "bidirectional"))
      (node (ref "GPIO40") (pin "25") (pinfunction "GND_25") (pintype "bidirectional"))
      (node (ref "GPIO40") (pin "30") (pinfunction "GND_30") (pintype "bidirectional"))
      (node (ref "GPIO40") (pin "34") (pinfunction "GND_34") (pintype "bidirectional"))
      (node (ref "GPIO40") (pin "39") (pinfunction "GND_39") (pintype "bidirectional"))
      (node (ref "GPIO40") (pin "9") (pinfunction "GND_9") (pintype "bidirectional"))
      (node (ref "I2C") (pin "GND") (pinfunction "GND_GND") (pintype "bidirectional"))
      (node (ref "IC1") (pin "2") (pinfunction "GND_2") (pintype "power_in"))
      (node (ref "IC2") (pin "1") (pinfunction "A0_1") (pintype "bidirectional"))
      (node (ref "IC2") (pin "14") (pinfunction "VSS_14") (pintype "bidirectional"))
      (node (ref "IC2") (pin "2") (pinfunction "A1_2") (pintype "bidirectional"))
      (node (ref "IC2") (pin "24") (pinfunction "A5_24") (pintype "bidirectional"))
      (node (ref "IC2") (pin "3") (pinfunction "A2_3") (pintype "bidirectional"))
      (node (ref "IC2") (pin "4") (pinfunction "A3_4") (pintype "bidirectional"))
      (node (ref "IC2") (pin "5") (pinfunction "A4_5") (pintype "bidirectional"))
      (node (ref "LED1") (pin "GND") (pinfunction "GND_GND") (pintype "bidirectional"))
      (node (ref "MOTOR") (pin "1") (pinfunction "1:GND_1") (pintype "bidirectional"))
      (node (ref "Q1") (pin "S") (pinfunction "S_S") (pintype "passive"))
      (node (ref "Q2") (pin "S") (pinfunction "S_S") (pintype "passive"))
      (node (ref "Q3") (pin "S") (pinfunction "S_S") (pintype "passive"))
      (node (ref "Q4") (pin "S") (pinfunction "S_S") (pintype "passive"))
      (node (ref "Q5") (pin "S") (pinfunction "S_S") (pintype "passive"))
      (node (ref "R1") (pin "1") (pinfunction "1_1") (pintype "bidirectional"))
      (node (ref "R13") (pin "2") (pinfunction "2_2") (pintype "bidirectional"))
      (node (ref "R17") (pin "1") (pinfunction "1_1") (pintype "bidirectional"))
      (node (ref "R24") (pin "2") (pinfunction "2_2") (pintype "bidirectional"))
      (node (ref "R28") (pin "1") (pinfunction "1_1") (pintype "bidirectional"))
      (node (ref "R3") (pin "1") (pinfunction "1_1") (pintype "bidirectional"))
      (node (ref "R32") (pin "2") (pinfunction "2_2") (pintype "bidirectional"))
      (node (ref "R33") (pin "2") (pinfunction "2_2") (pintype "bidirectional"))
      (node (ref "R36") (pin "1") (pinfunction "1_1") (pintype "bidirectional"))
      (node (ref "R40") (pin "2") (pinfunction "2_2") (pintype "bidirectional"))
      (node (ref "R41") (pin "2") (pinfunction "2_2") (pintype "bidirectional"))
      (node (ref "R42") (pin "2") (pinfunction "2_2") (pintype "bidirectional"))
      (node (ref "R45") (pin "1") (pinfunction "1_1") (pintype "bidirectional"))
      (node (ref "R46") (pin "2") (pinfunction "2_2") (pintype "bidirectional"))
      (node (ref "R49") (pin "1") (pinfunction "1_1") (pintype "bidirectional"))
      (node (ref "R55") (pin "2") (pinfunction "2_2") (pintype "bidirectional"))
      (node (ref "R57") (pin "1") (pinfunction "1_1") (pintype "bidirectional"))
      (node (ref "R58") (pin "1") (pinfunction "1_1") (pintype "bidirectional"))
      (node (ref "R6") (pin "2") (pinfunction "2_2") (pintype "bidirectional"))
      (node (ref "R60") (pin "2") (pinfunction "2_2") (pintype "bidirectional"))
      (node (ref "R62") (pin "2") (pinfunction "2_2") (pintype "bidirectional"))
      (node (ref "R65") (pin "1") (pinfunction "1_1") (pintype "bidirectional"))
      (node (ref "R66") (pin "2") (pinfunction "2_2") (pintype "bidirectional"))
      (node (ref "R68") (pin "2") (pinfunction "2_2") (pintype "bidirectional"))
      (node (ref "R7") (pin "2") (pinfunction "2_2") (pintype "bidirectional"))
      (node (ref "R9") (pin "1") (pinfunction "1_1") (pintype "bidirectional"))
      (node (ref "SPI-LED") (pin "GND") (pinfunction "GND_GND") (pintype "bidirectional"))
      (node (ref "ST") (pin "3") (pinfunction "3_3") (pintype "power_in"))
      (node (ref "T1") (pin "1") (pinfunction "1:GND(EMITTER)_1") (pintype "passive"))
      (node (ref "TH") (pin "3") (pinfunction "3_3") (pintype "power_in"))
      (node (ref "U$1") (pin "15") (pinfunction "15:E_15") (pintype "bidirectional"))
      (node (ref "U$1") (pin "8") (pinfunction "8:GND_8") (pintype "bidirectional"))
      (node (ref "U$10") (pin "1") (pinfunction "1:OE_1") (pintype "input"))
      (node (ref "U$10") (pin "3") (pinfunction "3:GND_3") (pintype "power_in"))
      (node (ref "U$11") (pin "#2") (pinfunction "2:CASE_GND_#2") (pintype "bidirectional"))
      (node (ref "U$13") (pin "18") (pinfunction "18:COM2_18") (pintype "bidirectional"))
      (node (ref "U$13") (pin "2") (pinfunction "2:GND_2") (pintype "power_in"))
      (node (ref "U$13") (pin "25") (pinfunction "25:GNDIO_25") (pintype "power_in"))
      (node (ref "U$14") (pin "1:GND_J3") (pinfunction "1:GND_J3_1:GND_J3") (pintype "bidirectional"))
      (node (ref "U$14") (pin "1:GND_J3R") (pinfunction "1:GND_J3_1:GND_J3R") (pintype "bidirectional"))
      (node (ref "U$14") (pin "21:GND_J3") (pinfunction "21:GND_J3_21:GND_J3") (pintype "power_in"))
      (node (ref "U$14") (pin "21:GND_J3_R") (pinfunction "21:GND_J3_21:GND_J3_R") (pintype "power_in"))
      (node (ref "U$14") (pin "22:GND_J1") (pinfunction "22:GND_J1_22:GND_J1") (pintype "power_in"))
      (node (ref "U$14") (pin "22:GND_J1L") (pinfunction "22:GND_J1_22:GND_J1L") (pintype "power_in"))
      (node (ref "U$14") (pin "22:GND_J3") (pinfunction "22:GND_J3_22:GND_J3") (pintype "power_in"))
      (node (ref "U$14") (pin "22:GND_J3_R") (pinfunction "22:GND_J3_22:GND_J3_R") (pintype "power_in"))
      (node (ref "U$3") (pin "4") (pinfunction "4:GND_4") (pintype "power_in"))
      (node (ref "U$5") (pin "4") (pinfunction "4:GND_4") (pintype "power_in"))
      (node (ref "U$9") (pin "1") (pinfunction "1:OE_1") (pintype "input"))
      (node (ref "U$9") (pin "3") (pinfunction "3:GND_3") (pintype "power_in"))
      (node (ref "U1") (pin "5") (pinfunction "5:GND_5") (pintype "bidirectional"))
      (node (ref "U7") (pin "10") (pinfunction "D3_10") (pintype "bidirectional"))
      (node (ref "U7") (pin "14") (pinfunction "E/RD#_14") (pintype "bidirectional"))
      (node (ref "U7") (pin "15") (pinfunction "R/W#_15") (pintype "bidirectional"))
      (node (ref "U7") (pin "18") (pinfunction "CS#_18") (pintype "bidirectional"))
      (node (ref "U7") (pin "19") (pinfunction "BS2_19") (pintype "bidirectional"))
      (node (ref "U7") (pin "2") (pinfunction "VLSS_2") (pintype "bidirectional"))
      (node (ref "U7") (pin "21") (pinfunction "BS0_21") (pintype "bidirectional"))
      (node (ref "U7") (pin "23") (pinfunction "VSS_23") (pintype "bidirectional"))
      (node (ref "U7") (pin "6") (pinfunction "D7_6") (pintype "bidirectional"))
      (node (ref "U7") (pin "7") (pinfunction "D6_7") (pintype "bidirectional"))
      (node (ref "U7") (pin "8") (pinfunction "D5_8") (pintype "bidirectional"))
      (node (ref "U7") (pin "9") (pinfunction "D4_9") (pintype "bidirectional"))
    )
    (net (code "71") (name "M_SENSOR1") (class "Default")
      (node (ref "R47") (pin "1") (pinfunction "1_1") (pintype "bidirectional"))
      (node (ref "U$14") (pin "9:GPIO16") (pinfunction "9:GPIO16_9:GPIO16") (pintype "bidirectional"))
      (node (ref "U$14") (pin "9:GPIO16_L") (pinfunction "9:GPIO16_9:GPIO16_L") (pintype "bidirectional"))
      (node (ref "U$3") (pin "7") (pinfunction "7:1Y_7") (pintype "open_collector"))
    )
    (net (code "72") (name "M_SENSOR2") (class "Default")
      (node (ref "R48") (pin "1") (pinfunction "1_1") (pintype "bidirectional"))
      (node (ref "U$14") (pin "10:GPIO17") (pinfunction "10:GPIO17_10:GPIO17") (pintype "bidirectional"))
      (node (ref "U$14") (pin "10:GPIO17_L") (pinfunction "10:GPIO17_10:GPIO17_L") (pintype "bidirectional"))
      (node (ref "U$3") (pin "2") (pinfunction "2:3Y_2") (pintype "open_collector"))
    )
    (net (code "73") (name "M_SENSOR3") (class "Default")
      (node (ref "R59") (pin "1") (pinfunction "1_1") (pintype "bidirectional"))
      (node (ref "U$14") (pin "11:GPIO18") (pinfunction "11:GPIO18_11:GPIO18") (pintype "bidirectional"))
      (node (ref "U$14") (pin "11:GPIO18_L") (pinfunction "11:GPIO18_11:GPIO18_L") (pintype "bidirectional"))
      (node (ref "U$3") (pin "5") (pinfunction "5:2Y_5") (pintype "open_collector"))
    )
    (net (code "74") (name "Net-(C12-Pad2)") (class "Default")
      (node (ref "C12") (pin "2") (pinfunction "2_2") (pintype "passive"))
      (node (ref "D1") (pin "ANODE") (pinfunction "ANODE_ANODE") (pintype "bidirectional"))
      (node (ref "R25") (pin "2") (pinfunction "2_2") (pintype "bidirectional"))
      (node (ref "R31") (pin "1") (pinfunction "1_1") (pintype "bidirectional"))
    )
    (net (code "75") (name "Net-(CH4-Pad1)") (class "Default")
      (node (ref "CH4") (pin "1") (pinfunction "1_1") (pintype "bidirectional"))
      (node (ref "R54") (pin "2") (pinfunction "2_2") (pintype "bidirectional"))
    )
    (net (code "76") (name "Net-(CH5-Pad1)") (class "Default")
      (node (ref "CH5") (pin "1") (pinfunction "1_1") (pintype "bidirectional"))
      (node (ref "R61") (pin "2") (pinfunction "2_2") (pintype "bidirectional"))
    )
    (net (code "77") (name "Net-(EXT1-Pad3:DOUT)") (class "Default")
      (node (ref "EXT1") (pin "3:DOUT") (pinfunction "3:DOUT_3:DOUT") (pintype "input"))
      (node (ref "R18") (pin "2") (pinfunction "2_2") (pintype "bidirectional"))
      (node (ref "R41") (pin "1") (pinfunction "1_1") (pintype "bidirectional"))
    )
    (net (code "78") (name "Net-(EXT1-Pad4:BCLK)") (class "Default")
      (node (ref "EXT1") (pin "4:BCLK") (pinfunction "4:BCLK_4:BCLK") (pintype "input"))
      (node (ref "R30") (pin "2") (pinfunction "2_2") (pintype "bidirectional"))
    )
    (net (code "79") (name "Net-(EXT1-Pad5:LRCLK)") (class "Default")
      (node (ref "EXT1") (pin "5:LRCLK") (pinfunction "5:LRCLK_5:LRCLK") (pintype "input"))
      (node (ref "R38") (pin "2") (pinfunction "2_2") (pintype "bidirectional"))
    )
    (net (code "80") (name "Net-(IC1-BYPASS)") (class "Default")
      (node (ref "C6") (pin "2") (pinfunction "2_2") (pintype "passive"))
      (node (ref "IC1") (pin "4") (pinfunction "BYPASS_4") (pintype "bidirectional"))
    )
    (net (code "81") (name "Net-(IC2-EXTCLK)") (class "Default")
      (node (ref "C3") (pin "2") (pinfunction "2_2") (pintype "passive"))
      (node (ref "IC2") (pin "25") (pinfunction "EXTCLK_25") (pintype "bidirectional"))
      (node (ref "R1") (pin "2") (pinfunction "2_2") (pintype "bidirectional"))
      (node (ref "U$11") (pin "#3") (pinfunction "3:OUTPUT_#3") (pintype "bidirectional"))
    )
    (net (code "82") (name "Net-(IC2-LED14)") (class "Default")
      (node (ref "IC2") (pin "21") (pinfunction "LED14_21") (pintype "bidirectional"))
      (node (ref "TP2") (pin "TP") (pinfunction "TP_TP") (pintype "passive"))
    )
    (net (code "83") (name "Net-(IC2-OE)") (class "Default")
      (node (ref "IC2") (pin "23") (pinfunction "OE_23") (pintype "bidirectional"))
      (node (ref "R3") (pin "2") (pinfunction "2_2") (pintype "bidirectional"))
    )
    (net (code "84") (name "Net-(Q1-PadG)") (class "Default")
      (node (ref "Q1") (pin "G") (pinfunction "G_G") (pintype "passive"))
      (node (ref "R54") (pin "1") (pinfunction "1_1") (pintype "bidirectional"))
      (node (ref "R55") (pin "1") (pinfunction "1_1") (pintype "bidirectional"))
    )
    (net (code "85") (name "Net-(Q2-PadG)") (class "Default")
      (node (ref "Q2") (pin "G") (pinfunction "G_G") (pintype "passive"))
      (node (ref "R61") (pin "1") (pinfunction "1_1") (pintype "bidirectional"))
      (node (ref "R62") (pin "1") (pinfunction "1_1") (pintype "bidirectional"))
    )
    (net (code "86") (name "Net-(Q3-PadG)") (class "Default")
      (node (ref "Q3") (pin "G") (pinfunction "G_G") (pintype "passive"))
      (node (ref "R24") (pin "1") (pinfunction "1_1") (pintype "bidirectional"))
      (node (ref "R8") (pin "1") (pinfunction "1_1") (pintype "bidirectional"))
    )
    (net (code "87") (name "Net-(Q4-PadG)") (class "Default")
      (node (ref "Q4") (pin "G") (pinfunction "G_G") (pintype "passive"))
      (node (ref "R33") (pin "1") (pinfunction "1_1") (pintype "bidirectional"))
      (node (ref "R35") (pin "2") (pinfunction "2_2") (pintype "bidirectional"))
    )
    (net (code "88") (name "Net-(Q5-PadG)") (class "Default")
      (node (ref "Q5") (pin "G") (pinfunction "G_G") (pintype "passive"))
      (node (ref "R32") (pin "1") (pinfunction "1_1") (pintype "bidirectional"))
      (node (ref "R34") (pin "2") (pinfunction "2_2") (pintype "bidirectional"))
    )
    (net (code "89") (name "Net-(R7-Pad1)") (class "Default")
      (node (ref "R7") (pin "1") (pinfunction "1_1") (pintype "bidirectional"))
      (node (ref "RCPWR") (pin "CATHODE") (pinfunction "CATHODE_CATHODE") (pintype "passive"))
    )
    (net (code "90") (name "Net-(R63-Pad1)") (class "Default")
      (node (ref "R63") (pin "1") (pinfunction "1_1") (pintype "bidirectional"))
      (node (ref "U$14") (pin "2:GPIO43") (pinfunction "2:GPIO43/U0TXD_2:GPIO43") (pintype "bidirectional"))
      (node (ref "U$14") (pin "2:GPIO43_R") (pinfunction "2:GPIO43/U0TXD_2:GPIO43_R") (pintype "bidirectional"))
    )
    (net (code "91") (name "Net-(R64-Pad1)") (class "Default")
      (node (ref "R64") (pin "1") (pinfunction "1_1") (pintype "bidirectional"))
      (node (ref "U$14") (pin "3:GPIO44") (pinfunction "3:GPIO44/U0RXD_3:GPIO44") (pintype "bidirectional"))
      (node (ref "U$14") (pin "3:GPIO44_R") (pinfunction "3:GPIO44/U0RXD_3:GPIO44_R") (pintype "bidirectional"))
    )
    (net (code "92") (name "Net-(R78-Pad2)") (class "Default")
      (node (ref "R78") (pin "2") (pinfunction "2_2") (pintype "bidirectional"))
      (node (ref "U$14") (pin "16:GPIO10") (pinfunction "16:GPIO10_16:GPIO10") (pintype "bidirectional"))
      (node (ref "U$14") (pin "16:GPIO10_L") (pinfunction "16:GPIO10_16:GPIO10_L") (pintype "bidirectional"))
    )
    (net (code "93") (name "Net-(R79-Pad2)") (class "Default")
      (node (ref "R79") (pin "2") (pinfunction "2_2") (pintype "bidirectional"))
      (node (ref "U$14") (pin "19:GPIO13") (pinfunction "19:GPIO13_19:GPIO13") (pintype "bidirectional"))
      (node (ref "U$14") (pin "19:GPIO13_L") (pinfunction "19:GPIO13_19:GPIO13_L") (pintype "bidirectional"))
    )
    (net (code "94") (name "Net-(U$1-2:A0)") (class "Default")
      (node (ref "R75") (pin "2") (pinfunction "2_2") (pintype "bidirectional"))
      (node (ref "U$1") (pin "2") (pinfunction "2:A0_2") (pintype "bidirectional"))
      (node (ref "U$5") (pin "7") (pinfunction "7:1Y_7") (pintype "open_collector"))
    )
    (net (code "95") (name "Net-(U$1-5:A1)") (class "Default")
      (node (ref "R74") (pin "2") (pinfunction "2_2") (pintype "bidirectional"))
      (node (ref "U$1") (pin "5") (pinfunction "5:A1_5") (pintype "bidirectional"))
      (node (ref "U$5") (pin "5") (pinfunction "5:2Y_5") (pintype "open_collector"))
    )
    (net (code "96") (name "Net-(U$1-10:B2)") (class "Default")
      (node (ref "R45") (pin "2") (pinfunction "2_2") (pintype "bidirectional"))
      (node (ref "U$1") (pin "10") (pinfunction "10:B2_10") (pintype "bidirectional"))
    )
    (net (code "97") (name "Net-(U$1-11:A2)") (class "Default")
      (node (ref "R17") (pin "2") (pinfunction "2_2") (pintype "bidirectional"))
      (node (ref "U$1") (pin "11") (pinfunction "11:A2_11") (pintype "bidirectional"))
    )
    (net (code "98") (name "Net-(U$1-13:B3)") (class "Default")
      (node (ref "R9") (pin "2") (pinfunction "2_2") (pintype "bidirectional"))
      (node (ref "U$1") (pin "13") (pinfunction "13:B3_13") (pintype "bidirectional"))
    )
    (net (code "99") (name "Net-(U$1-14:A3)") (class "Default")
      (node (ref "R65") (pin "2") (pinfunction "2_2") (pintype "bidirectional"))
      (node (ref "U$1") (pin "14") (pinfunction "14:A3_14") (pintype "bidirectional"))
    )
    (net (code "100") (name "Net-(U$5-6:3A)") (class "Default")
      (node (ref "R73") (pin "2") (pinfunction "2_2") (pintype "bidirectional"))
      (node (ref "U$5") (pin "6") (pinfunction "6:3A_6") (pintype "input"))
    )
    (net (code "101") (name "Net-(U$9-4:Y)") (class "Default")
      (node (ref "LED1") (pin "SDI") (pinfunction "SDI_SDI") (pintype "bidirectional"))
      (node (ref "U$9") (pin "4") (pinfunction "4:Y_4") (pintype "output"))
    )
    (net (code "102") (name "Net-(U$10-4:Y)") (class "Default")
      (node (ref "LED1") (pin "CKI") (pinfunction "CKI_CKI") (pintype "bidirectional"))
      (node (ref "U$10") (pin "4") (pinfunction "4:Y_4") (pintype "output"))
    )
    (net (code "103") (name "Net-(U$13-4:NBOOT)") (class "Default")
      (node (ref "R70") (pin "1") (pinfunction "1_1") (pintype "bidirectional"))
      (node (ref "U$13") (pin "4") (pinfunction "4:NBOOT_4") (pintype "input"))
    )
    (net (code "104") (name "Net-(U$13-5:PS1)") (class "Default")
      (node (ref "R49") (pin "2") (pinfunction "2_2") (pintype "bidirectional"))
      (node (ref "U$13") (pin "5") (pinfunction "5:PS1_5") (pintype "input"))
    )
    (net (code "105") (name "Net-(U$13-6:PS0)") (class "Default")
      (node (ref "R57") (pin "2") (pinfunction "2_2") (pintype "bidirectional"))
      (node (ref "U$13") (pin "6") (pinfunction "6:PS0_6") (pintype "input"))
    )
    (net (code "106") (name "Net-(U$13-7:SWDIO)") (class "Default")
      (node (ref "TP4") (pin "TP") (pinfunction "TP_TP") (pintype "passive"))
      (node (ref "U$13") (pin "7") (pinfunction "7:SWDIO_7") (pintype "bidirectional"))
    )
    (net (code "107") (name "Net-(U$13-8:SWCLK)") (class "Default")
      (node (ref "TP5") (pin "TP") (pinfunction "TP_TP") (pintype "passive"))
      (node (ref "U$13") (pin "8") (pinfunction "8:SWCLK_8") (pintype "input"))
    )
    (net (code "108") (name "Net-(U$13-9:CAP)") (class "Default")
      (node (ref "C21") (pin "2") (pinfunction "2_2") (pintype "passive"))
      (node (ref "U$13") (pin "9") (pinfunction "9:CAP_9") (pintype "bidirectional"))
    )
    (net (code "109") (name "Net-(U$13-10:BL_IND)") (class "Default")
      (node (ref "TP3") (pin "TP") (pinfunction "TP_TP") (pintype "passive"))
      (node (ref "U$13") (pin "10") (pinfunction "10:BL_IND_10") (pintype "output"))
    )
    (net (code "110") (name "Net-(U$13-11:NRESET)") (class "Default")
      (node (ref "R69") (pin "1") (pinfunction "1_1") (pintype "bidirectional"))
      (node (ref "R71") (pin "2") (pinfunction "2_2") (pintype "bidirectional"))
      (node (ref "U$13") (pin "11") (pinfunction "11:NRESET_11") (pintype "bidirectional"))
    )
    (net (code "111") (name "Net-(U$13-17:COM3)") (class "Default")
      (node (ref "R58") (pin "2") (pinfunction "2_2") (pintype "bidirectional"))
      (node (ref "R72") (pin "1") (pinfunction "1_1") (pintype "bidirectional"))
      (node (ref "U$13") (pin "17") (pinfunction "17:COM3_17") (pintype "input"))
    )
    (net (code "112") (name "Net-(U$13-26:XOUT32)") (class "Default")
      (node (ref "C25") (pin "1") (pinfunction "1_1") (pintype "passive"))
      (node (ref "U$13") (pin "26") (pinfunction "26:XOUT32_26") (pintype "output"))
      (node (ref "X1") (pin "2") (pinfunction "P$2_2") (pintype "bidirectional"))
    )
    (net (code "113") (name "Net-(U$13-27:XIN32)") (class "Default")
      (node (ref "C24") (pin "1") (pinfunction "1_1") (pintype "passive"))
      (node (ref "U$13") (pin "27") (pinfunction "27:XIN32_27") (pintype "input"))
      (node (ref "X1") (pin "1") (pinfunction "P$1_1") (pintype "bidirectional"))
    )
    (net (code "114") (name "Net-(U$14-1:3V3-Pad1:3V3_L)") (class "Default")
      (node (ref "U$14") (pin "1:3V3") (pinfunction "1:3V3_1:3V3") (pintype "power_in"))
      (node (ref "U$14") (pin "1:3V3_L") (pinfunction "1:3V3_1:3V3_L") (pintype "power_in"))
    )
    (net (code "115") (name "Net-(U$14-2:3V3-Pad2:3V3_L)") (class "Default")
      (node (ref "U$14") (pin "2:3V3") (pinfunction "2:3V3_2:3V3") (pintype "power_in"))
      (node (ref "U$14") (pin "2:3V3_L") (pinfunction "2:3V3_2:3V3_L") (pintype "power_in"))
    )
    (net (code "116") (name "Net-(U$14-3:RST(CHIP_PU)-Pad3:RST)") (class "Default")
      (node (ref "U$14") (pin "3:RST") (pinfunction "3:RST(CHIP_PU)_3:RST") (pintype "input"))
      (node (ref "U$14") (pin "3:RST_L") (pinfunction "3:RST(CHIP_PU)_3:RST_L") (pintype "input"))
    )
    (net (code "117") (name "Net-(U$14-4:GPIO1-Pad4:GPIO1_R)") (class "Default")
      (node (ref "U$14") (pin "4:GPIO1") (pinfunction "4:GPIO1_4:GPIO1") (pintype "bidirectional"))
      (node (ref "U$14") (pin "4:GPIO1_R") (pinfunction "4:GPIO1_4:GPIO1_R") (pintype "bidirectional"))
    )
    (net (code "118") (name "Net-(U$14-5:GPOP2-Pad5:GPIO2)") (class "Default")
      (node (ref "U$14") (pin "5:GPIO2") (pinfunction "5:GPOP2_5:GPIO2") (pintype "bidirectional"))
      (node (ref "U$14") (pin "5:GPIO2_R") (pinfunction "5:GPOP2_5:GPIO2_R") (pintype "bidirectional"))
    )
    (net (code "119") (name "Net-(U$14-6:GPIO42-Pad6:GPIO42_R)") (class "Default")
      (node (ref "U$14") (pin "6:GPIO42") (pinfunction "6:GPIO42_6:GPIO42") (pintype "bidirectional"))
      (node (ref "U$14") (pin "6:GPIO42_R") (pinfunction "6:GPIO42_6:GPIO42_R") (pintype "bidirectional"))
    )
    (net (code "120") (name "Net-(U$14-7:GPIO41-Pad7:GPIO41_R)") (class "Default")
      (node (ref "U$14") (pin "7:GPIO41") (pinfunction "7:GPIO41_7:GPIO41") (pintype "bidirectional"))
      (node (ref "U$14") (pin "7:GPIO41_R") (pinfunction "7:GPIO41_7:GPIO41_R") (pintype "bidirectional"))
    )
    (net (code "121") (name "Net-(U$14-8:GPIO40-Pad8:GPIO40_R)") (class "Default")
      (node (ref "U$14") (pin "8:GPIO40") (pinfunction "8:GPIO40_8:GPIO40") (pintype "bidirectional"))
      (node (ref "U$14") (pin "8:GPIO40_R") (pinfunction "8:GPIO40_8:GPIO40_R") (pintype "bidirectional"))
    )
    (net (code "122") (name "Net-(U$14-9:GPIO39-Pad9:GPIO39_R)") (class "Default")
      (node (ref "U$14") (pin "9:GPIO39") (pinfunction "9:GPIO39_9:GPIO39") (pintype "bidirectional"))
      (node (ref "U$14") (pin "9:GPIO39_R") (pinfunction "9:GPIO39_9:GPIO39_R") (pintype "bidirectional"))
    )
    (net (code "123") (name "Net-(U$14-10:GPIO38-Pad10:GPIO38_R)") (class "Default")
      (node (ref "U$14") (pin "10:GPIO38") (pinfunction "10:GPIO38_10:GPIO38") (pintype "bidirectional"))
      (node (ref "U$14") (pin "10:GPIO38_R") (pinfunction "10:GPIO38_10:GPIO38_R") (pintype "bidirectional"))
    )
    (net (code "124") (name "Net-(U$14-11:GPIO37-Pad11:GPIO37_R)") (class "Default")
      (node (ref "U$14") (pin "11:GPIO37") (pinfunction "11:GPIO37_11:GPIO37") (pintype "bidirectional"))
      (node (ref "U$14") (pin "11:GPIO37_R") (pinfunction "11:GPIO37_11:GPIO37_R") (pintype "bidirectional"))
    )
    (net (code "125") (name "Net-(U$14-12:GPIO36-Pad12:GPIO36_R)") (class "Default")
      (node (ref "U$14") (pin "12:GPIO36") (pinfunction "12:GPIO36_12:GPIO36") (pintype "bidirectional"))
      (node (ref "U$14") (pin "12:GPIO36_R") (pinfunction "12:GPIO36_12:GPIO36_R") (pintype "bidirectional"))
    )
    (net (code "126") (name "Net-(U$14-13:GPIO3{slash}JTAG-Pad13:GPIO3)") (class "Default")
      (node (ref "U$14") (pin "13:GPIO3") (pinfunction "13:GPIO3/JTAG_13:GPIO3") (pintype "input"))
      (node (ref "U$14") (pin "13:GPIO3_L") (pinfunction "13:GPIO3/JTAG_13:GPIO3_L") (pintype "input"))
    )
    (net (code "127") (name "Net-(U$14-13:GPIO35-Pad13:GPIO35_R)") (class "Default")
      (node (ref "U$14") (pin "13:GPIO35") (pinfunction "13:GPIO35_13:GPIO35") (pintype "bidirectional"))
      (node (ref "U$14") (pin "13:GPIO35_R") (pinfunction "13:GPIO35_13:GPIO35_R") (pintype "bidirectional"))
    )
    (net (code "128") (name "Net-(U$14-14:GPIO0{slash}BOOT-Pad14:GPIO0)") (class "Default")
      (node (ref "U$14") (pin "14:GPIO0") (pinfunction "14:GPIO0/BOOT_14:GPIO0") (pintype "input"))
      (node (ref "U$14") (pin "14:GPIO0_R") (pinfunction "14:GPIO0/BOOT_14:GPIO0_R") (pintype "input"))
    )
    (net (code "129") (name "Net-(U$14-14:GPIO46{slash}LOG-Pad14:GPIO46)") (class "Default")
      (node (ref "U$14") (pin "14:GPIO46") (pinfunction "14:GPIO46/LOG_14:GPIO46") (pintype "input"))
      (node (ref "U$14") (pin "14:GPIO46_L") (pinfunction "14:GPIO46/LOG_14:GPIO46_L") (pintype "input"))
    )
    (net (code "130") (name "Net-(U$14-16:GPIO48-Pad16:GPIO48_R)") (class "Default")
      (node (ref "U$14") (pin "16:GPIO48") (pinfunction "16:GPIO48_16:GPIO48") (pintype "bidirectional"))
      (node (ref "U$14") (pin "16:GPIO48_R") (pinfunction "16:GPIO48_16:GPIO48_R") (pintype "bidirectional"))
    )
    (net (code "131") (name "Net-(U$14-18:GPIO21-Pad18:GPIO21_R)") (class "Default")
      (node (ref "U$14") (pin "18:GPIO21") (pinfunction "18:GPIO21_18:GPIO21") (pintype "bidirectional"))
      (node (ref "U$14") (pin "18:GPIO21_R") (pinfunction "18:GPIO21_18:GPIO21_R") (pintype "bidirectional"))
    )
    (net (code "132") (name "Net-(U$14-19:GPIO20{slash}USBD+-Pad19:GPIO20)") (class "Default")
      (node (ref "U$14") (pin "19:GPIO20") (pinfunction "19:GPIO20/USBD+_19:GPIO20") (pintype "bidirectional"))
      (node (ref "U$14") (pin "19:GPIO20_R") (pinfunction "19:GPIO20/USBD+_19:GPIO20_R") (pintype "bidirectional"))
    )
    (net (code "133") (name "Net-(U$14-20:GPIO14-Pad20:GPIO14_L)") (class "Default")
      (node (ref "U$14") (pin "20:GPIO14") (pinfunction "20:GPIO14_20:GPIO14") (pintype "bidirectional"))
      (node (ref "U$14") (pin "20:GPIO14_L") (pinfunction "20:GPIO14_20:GPIO14_L") (pintype "bidirectional"))
    )
    (net (code "134") (name "Net-(U$14-20:GPIO19{slash}USBD--Pad20:GPIO19)") (class "Default")
      (node (ref "U$14") (pin "20:GPIO19") (pinfunction "20:GPIO19/USBD-_20:GPIO19") (pintype "bidirectional"))
      (node (ref "U$14") (pin "20:GPIO19_R") (pinfunction "20:GPIO19/USBD-_20:GPIO19_R") (pintype "bidirectional"))
    )
    (net (code "135") (name "Net-(U1-1:AN1)") (class "Default")
      (node (ref "R16") (pin "1") (pinfunction "1_1") (pintype "bidirectional"))
      (node (ref "R29") (pin "1") (pinfunction "1_1") (pintype "bidirectional"))
      (node (ref "U1") (pin "1") (pinfunction "1:AN1_1") (pintype "bidirectional"))
    )
    (net (code "136") (name "Net-(U1-2:CA1)") (class "Default")
      (node (ref "Q5") (pin "D") (pinfunction "D_D") (pintype "passive"))
      (node (ref "R29") (pin "2") (pinfunction "2_2") (pintype "bidirectional"))
      (node (ref "U1") (pin "2") (pinfunction "2:CA1_2") (pintype "bidirectional"))
    )
    (net (code "137") (name "Net-(U1-3:CA2)") (class "Default")
      (node (ref "Q4") (pin "D") (pinfunction "D_D") (pintype "passive"))
      (node (ref "R27") (pin "1") (pinfunction "1_1") (pintype "bidirectional"))
      (node (ref "U1") (pin "3") (pinfunction "3:CA2_3") (pintype "bidirectional"))
    )
    (net (code "138") (name "Net-(U1-4:AN2)") (class "Default")
      (node (ref "R15") (pin "1") (pinfunction "1_1") (pintype "bidirectional"))
      (node (ref "R27") (pin "2") (pinfunction "2_2") (pintype "bidirectional"))
      (node (ref "U1") (pin "4") (pinfunction "4:AN2_4") (pintype "bidirectional"))
    )
    (net (code "139") (name "Net-(U2-A)") (class "Default")
      (node (ref "R26") (pin "1") (pinfunction "1_1") (pintype "bidirectional"))
      (node (ref "U2") (pin "1") (pinfunction "A_1") (pintype "passive"))
    )
    (net (code "140") (name "Net-(U2-C)") (class "Default")
      (node (ref "Q3") (pin "D") (pinfunction "D_D") (pintype "passive"))
      (node (ref "R53") (pin "2") (pinfunction "2_2") (pintype "bidirectional"))
      (node (ref "U2") (pin "2") (pinfunction "C_2") (pintype "passive"))
    )
    (net (code "141") (name "Net-(U3-A)") (class "Default")
      (node (ref "R56") (pin "1") (pinfunction "1_1") (pintype "bidirectional"))
      (node (ref "U3") (pin "1") (pinfunction "A_1") (pintype "passive"))
    )
    (net (code "142") (name "Net-(U3-C)") (class "Default")
      (node (ref "Q1") (pin "D") (pinfunction "D_D") (pintype "passive"))
      (node (ref "U3") (pin "2") (pinfunction "C_2") (pintype "passive"))
    )
    (net (code "143") (name "Net-(U4-A)") (class "Default")
      (node (ref "R67") (pin "1") (pinfunction "1_1") (pintype "bidirectional"))
      (node (ref "U4") (pin "1") (pinfunction "A_1") (pintype "passive"))
    )
    (net (code "144") (name "Net-(U4-C)") (class "Default")
      (node (ref "Q2") (pin "D") (pinfunction "D_D") (pintype "passive"))
      (node (ref "U4") (pin "2") (pinfunction "C_2") (pintype "passive"))
    )
    (net (code "145") (name "Net-(U7-BS1)") (class "Default")
      (node (ref "R19") (pin "2") (pinfunction "2_2") (pintype "bidirectional"))
      (node (ref "U7") (pin "20") (pinfunction "BS1_20") (pintype "bidirectional"))
    )
    (net (code "146") (name "Net-(U7-C1N)") (class "Default")
      (node (ref "C19") (pin "1") (pinfunction "1_1") (pintype "passive"))
      (node (ref "U7") (pin "26") (pinfunction "C1N_26") (pintype "bidirectional"))
    )
    (net (code "147") (name "Net-(U7-C1P)") (class "Default")
      (node (ref "C19") (pin "2") (pinfunction "2_2") (pintype "passive"))
      (node (ref "U7") (pin "27") (pinfunction "C1P_27") (pintype "bidirectional"))
    )
    (net (code "148") (name "Net-(U7-C2N)") (class "Default")
      (node (ref "C22") (pin "1") (pinfunction "1_1") (pintype "passive"))
      (node (ref "U7") (pin "28") (pinfunction "C2N_28") (pintype "bidirectional"))
    )
    (net (code "149") (name "Net-(U7-C2P)") (class "Default")
      (node (ref "C22") (pin "2") (pinfunction "2_2") (pintype "passive"))
      (node (ref "U7") (pin "29") (pinfunction "C2P_29") (pintype "bidirectional"))
    )
    (net (code "150") (name "Net-(U7-D{slash}C#)") (class "Default")
      (node (ref "R36") (pin "2") (pinfunction "2_2") (pintype "bidirectional"))
      (node (ref "R37") (pin "1") (pinfunction "1_1") (pintype "bidirectional"))
      (node (ref "U7") (pin "16") (pinfunction "D/C#_16") (pintype "bidirectional"))
    )
    (net (code "151") (name "Net-(U7-IREF)") (class "Default")
      (node (ref "R13") (pin "1") (pinfunction "1_1") (pintype "bidirectional"))
      (node (ref "U7") (pin "5") (pinfunction "IREF_5") (pintype "bidirectional"))
    )
    (net (code "152") (name "Net-(U7-VCC)") (class "Default")
      (node (ref "C13") (pin "2") (pinfunction "2_2") (pintype "passive"))
      (node (ref "U7") (pin "3") (pinfunction "VCC_3") (pintype "bidirectional"))
    )
    (net (code "153") (name "Net-(U7-VCOMH)") (class "Default")
      (node (ref "C16") (pin "2") (pinfunction "2_2") (pintype "passive"))
      (node (ref "U7") (pin "4") (pinfunction "VCOMH_4") (pintype "bidirectional"))
    )
    (net (code "154") (name "VSPI") (class "Default")
      (node (ref "R76") (pin "1") (pinfunction "1_1") (pintype "bidirectional"))
      (node (ref "R77") (pin "1") (pinfunction "1_1") (pintype "bidirectional"))
      (node (ref "R78") (pin "1") (pinfunction "1_1") (pintype "bidirectional"))
      (node (ref "R79") (pin "1") (pinfunction "1_1") (pintype "bidirectional"))
      (node (ref "U$14") (pin "15:GPIO45") (pinfunction "15:GPIO45/VSPI_15:GPIO45") (pintype "power_in"))
      (node (ref "U$14") (pin "15:GPIO45_R") (pinfunction "15:GPIO45/VSPI_15:GPIO45_R") (pintype "power_in"))
    )
    (net (code "155") (name "unconnected-(GPIO40-CE1-Pad26)") (class "Default")
      (node (ref "GPIO40") (pin "26") (pinfunction "CE1_26") (pintype "bidirectional"))
    )
    (net (code "156") (name "unconnected-(GPIO40-ID_SC-Pad28)") (class "Default")
      (node (ref "GPIO40") (pin "28") (pinfunction "ID_SC_28") (pintype "bidirectional"))
    )
    (net (code "157") (name "unconnected-(GPIO40-ID_SD-Pad27)") (class "Default")
      (node (ref "GPIO40") (pin "27") (pinfunction "ID_SD_27") (pintype "bidirectional"))
    )
    (net (code "158") (name "unconnected-(IC2-LED2-Pad8)") (class "Default")
      (node (ref "IC2") (pin "8") (pinfunction "LED2_8") (pintype "bidirectional"))
    )
    (net (code "159") (name "unconnected-(IC2-LED3-Pad9)") (class "Default")
      (node (ref "IC2") (pin "9") (pinfunction "LED3_9") (pintype "bidirectional"))
    )
    (net (code "160") (name "unconnected-(IC2-LED4-Pad10)") (class "Default")
      (node (ref "IC2") (pin "10") (pinfunction "LED4_10") (pintype "bidirectional"))
    )
    (net (code "161") (name "unconnected-(IC2-LED5-Pad11)") (class "Default")
      (node (ref "IC2") (pin "11") (pinfunction "LED5_11") (pintype "bidirectional"))
    )
    (net (code "162") (name "unconnected-(IC2-LED6-Pad12)") (class "Default")
      (node (ref "IC2") (pin "12") (pinfunction "LED6_12") (pintype "bidirectional"))
    )
    (net (code "163") (name "unconnected-(IC2-LED7-Pad13)") (class "Default")
      (node (ref "IC2") (pin "13") (pinfunction "LED7_13") (pintype "bidirectional"))
    )
    (net (code "164") (name "unconnected-(IC2-LED8-Pad15)") (class "Default")
      (node (ref "IC2") (pin "15") (pinfunction "LED8_15") (pintype "bidirectional"))
    )
    (net (code "165") (name "unconnected-(IC2-LED9-Pad16)") (class "Default")
      (node (ref "IC2") (pin "16") (pinfunction "LED9_16") (pintype "bidirectional"))
    )
    (net (code "166") (name "unconnected-(IC2-LED10-Pad17)") (class "Default")
      (node (ref "IC2") (pin "17") (pinfunction "LED10_17") (pintype "bidirectional"))
    )
    (net (code "167") (name "unconnected-(IC2-LED11-Pad18)") (class "Default")
      (node (ref "IC2") (pin "18") (pinfunction "LED11_18") (pintype "bidirectional"))
    )
    (net (code "168") (name "unconnected-(IC2-LED12-Pad19)") (class "Default")
      (node (ref "IC2") (pin "19") (pinfunction "LED12_19") (pintype "bidirectional"))
    )
    (net (code "169") (name "unconnected-(IC2-LED13-Pad20)") (class "Default")
      (node (ref "IC2") (pin "20") (pinfunction "LED13_20") (pintype "bidirectional"))
    )
    (net (code "170") (name "unconnected-(IC2-LED15-Pad22)") (class "Default")
      (node (ref "IC2") (pin "22") (pinfunction "LED15_22") (pintype "bidirectional"))
    )
    (net (code "171") (name "unconnected-(U$1-9:Y2-Pad9)") (class "Default")
      (node (ref "U$1") (pin "9") (pinfunction "9:Y2_9") (pintype "bidirectional"))
    )
    (net (code "172") (name "unconnected-(U$1-12:Y3-Pad12)") (class "Default")
      (node (ref "U$1") (pin "12") (pinfunction "12:Y3_12") (pintype "bidirectional"))
    )
    (net (code "173") (name "unconnected-(U$5-2:3Y-Pad2)") (class "Default")
      (node (ref "U$5") (pin "2") (pinfunction "2:3Y_2") (pintype "open_collector"))
    )
    (net (code "174") (name "unconnected-(U$13-1:PIN1-Pad1)") (class "Default")
      (node (ref "U$13") (pin "1") (pinfunction "1:PIN1_1") (pintype "no_connect"))
    )
    (net (code "175") (name "unconnected-(U$13-12:PIN12-Pad12)") (class "Default")
      (node (ref "U$13") (pin "12") (pinfunction "12:PIN12_12") (pintype "no_connect"))
    )
    (net (code "176") (name "unconnected-(U$13-13:PIN13-Pad13)") (class "Default")
      (node (ref "U$13") (pin "13") (pinfunction "13:PIN13_13") (pintype "no_connect"))
    )
    (net (code "177") (name "unconnected-(U$13-14:INT-Pad14)") (class "Default")
      (node (ref "U$13") (pin "14") (pinfunction "14:INT_14") (pintype "output"))
    )
    (net (code "178") (name "unconnected-(U$13-15:PIN15-Pad15)") (class "Default")
      (node (ref "U$13") (pin "15") (pinfunction "15:PIN15_15") (pintype "no_connect"))
    )
    (net (code "179") (name "unconnected-(U$13-16:PIN16-Pad16)") (class "Default")
      (node (ref "U$13") (pin "16") (pinfunction "16:PIN16_16") (pintype "no_connect"))
    )
    (net (code "180") (name "unconnected-(U$13-21:PIN21-Pad21)") (class "Default")
      (node (ref "U$13") (pin "21") (pinfunction "21:PIN21_21") (pintype "no_connect"))
    )
    (net (code "181") (name "unconnected-(U$13-22:PIN22-Pad22)") (class "Default")
      (node (ref "U$13") (pin "22") (pinfunction "22:PIN22_22") (pintype "no_connect"))
    )
    (net (code "182") (name "unconnected-(U$13-23:PIN23-Pad23)") (class "Default")
      (node (ref "U$13") (pin "23") (pinfunction "23:PIN23_23") (pintype "no_connect"))
    )
    (net (code "183") (name "unconnected-(U$13-24:PIN24-Pad24)") (class "Default")
      (node (ref "U$13") (pin "24") (pinfunction "24:PIN24_24") (pintype "no_connect"))
    )
    (net (code "184") (name "unconnected-(U7-NC-Pad1)") (class "Default")
      (node (ref "U7") (pin "1") (pinfunction "NC_1") (pintype "bidirectional"))
    )
    (net (code "185") (name "unconnected-(U7-NC-Pad24)") (class "Default")
      (node (ref "U7") (pin "24") (pinfunction "NC_24") (pintype "bidirectional"))
    )
    (net (code "186") (name "unconnected-(U7-NC-Pad30)") (class "Default")
      (node (ref "U7") (pin "30") (pinfunction "NC_30") (pintype "bidirectional"))
    )
  )
)
